# FPGA.net
KiCad netlist of a schematic drawn in Altium Designer
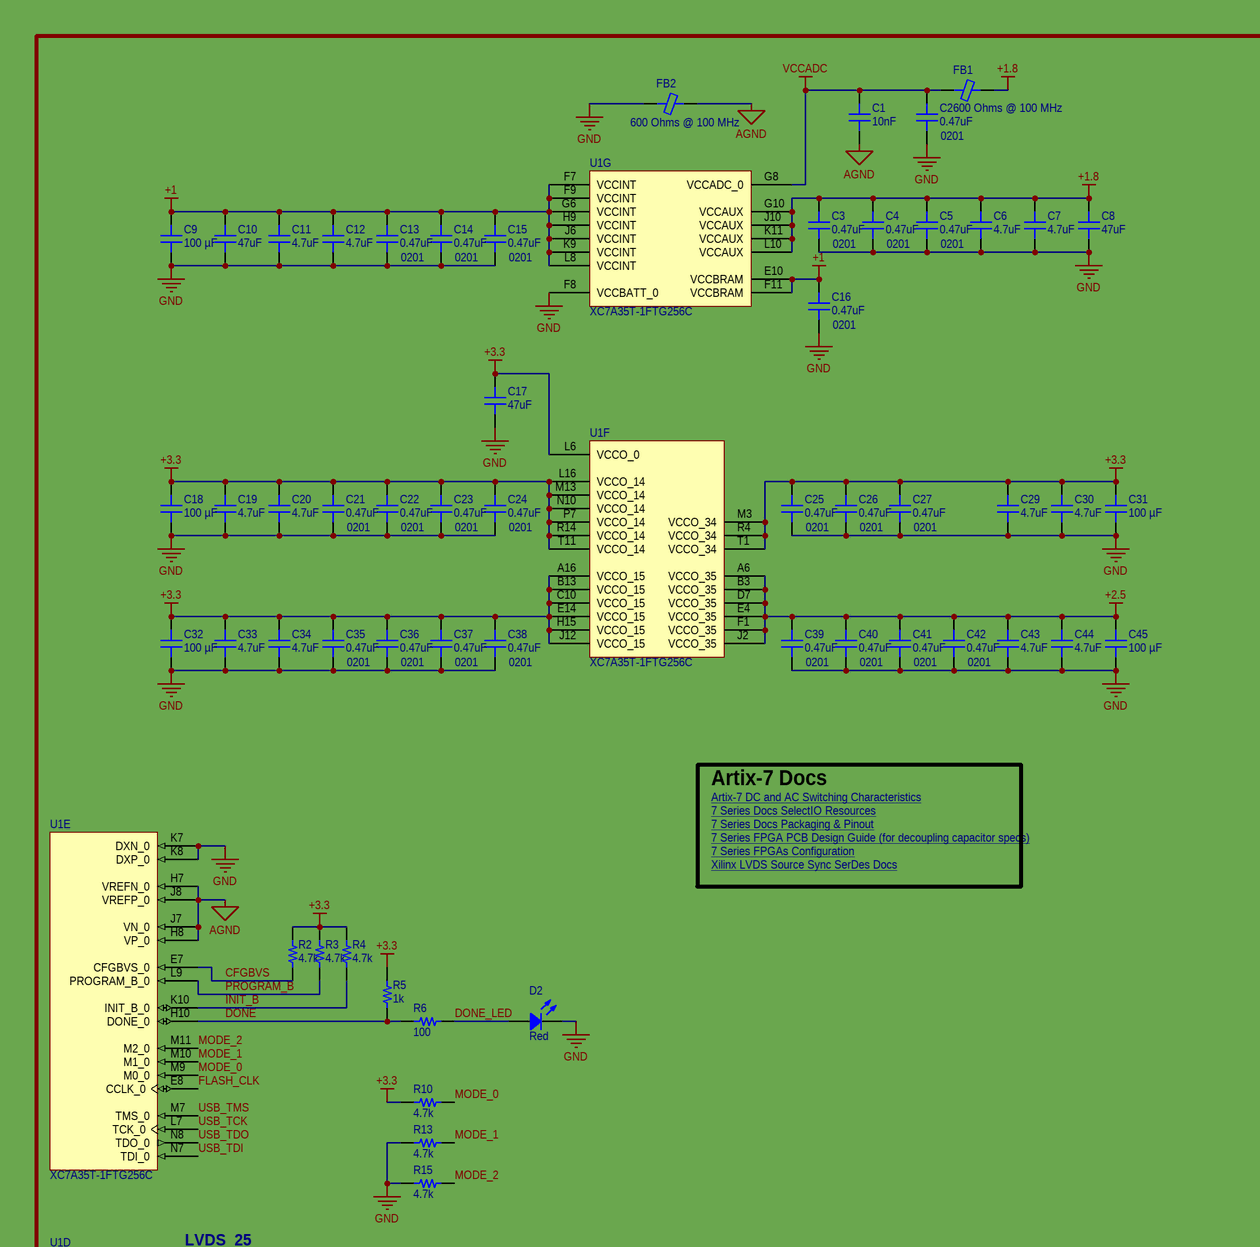
[diagram p0: FPGA.SchDoc, top left]
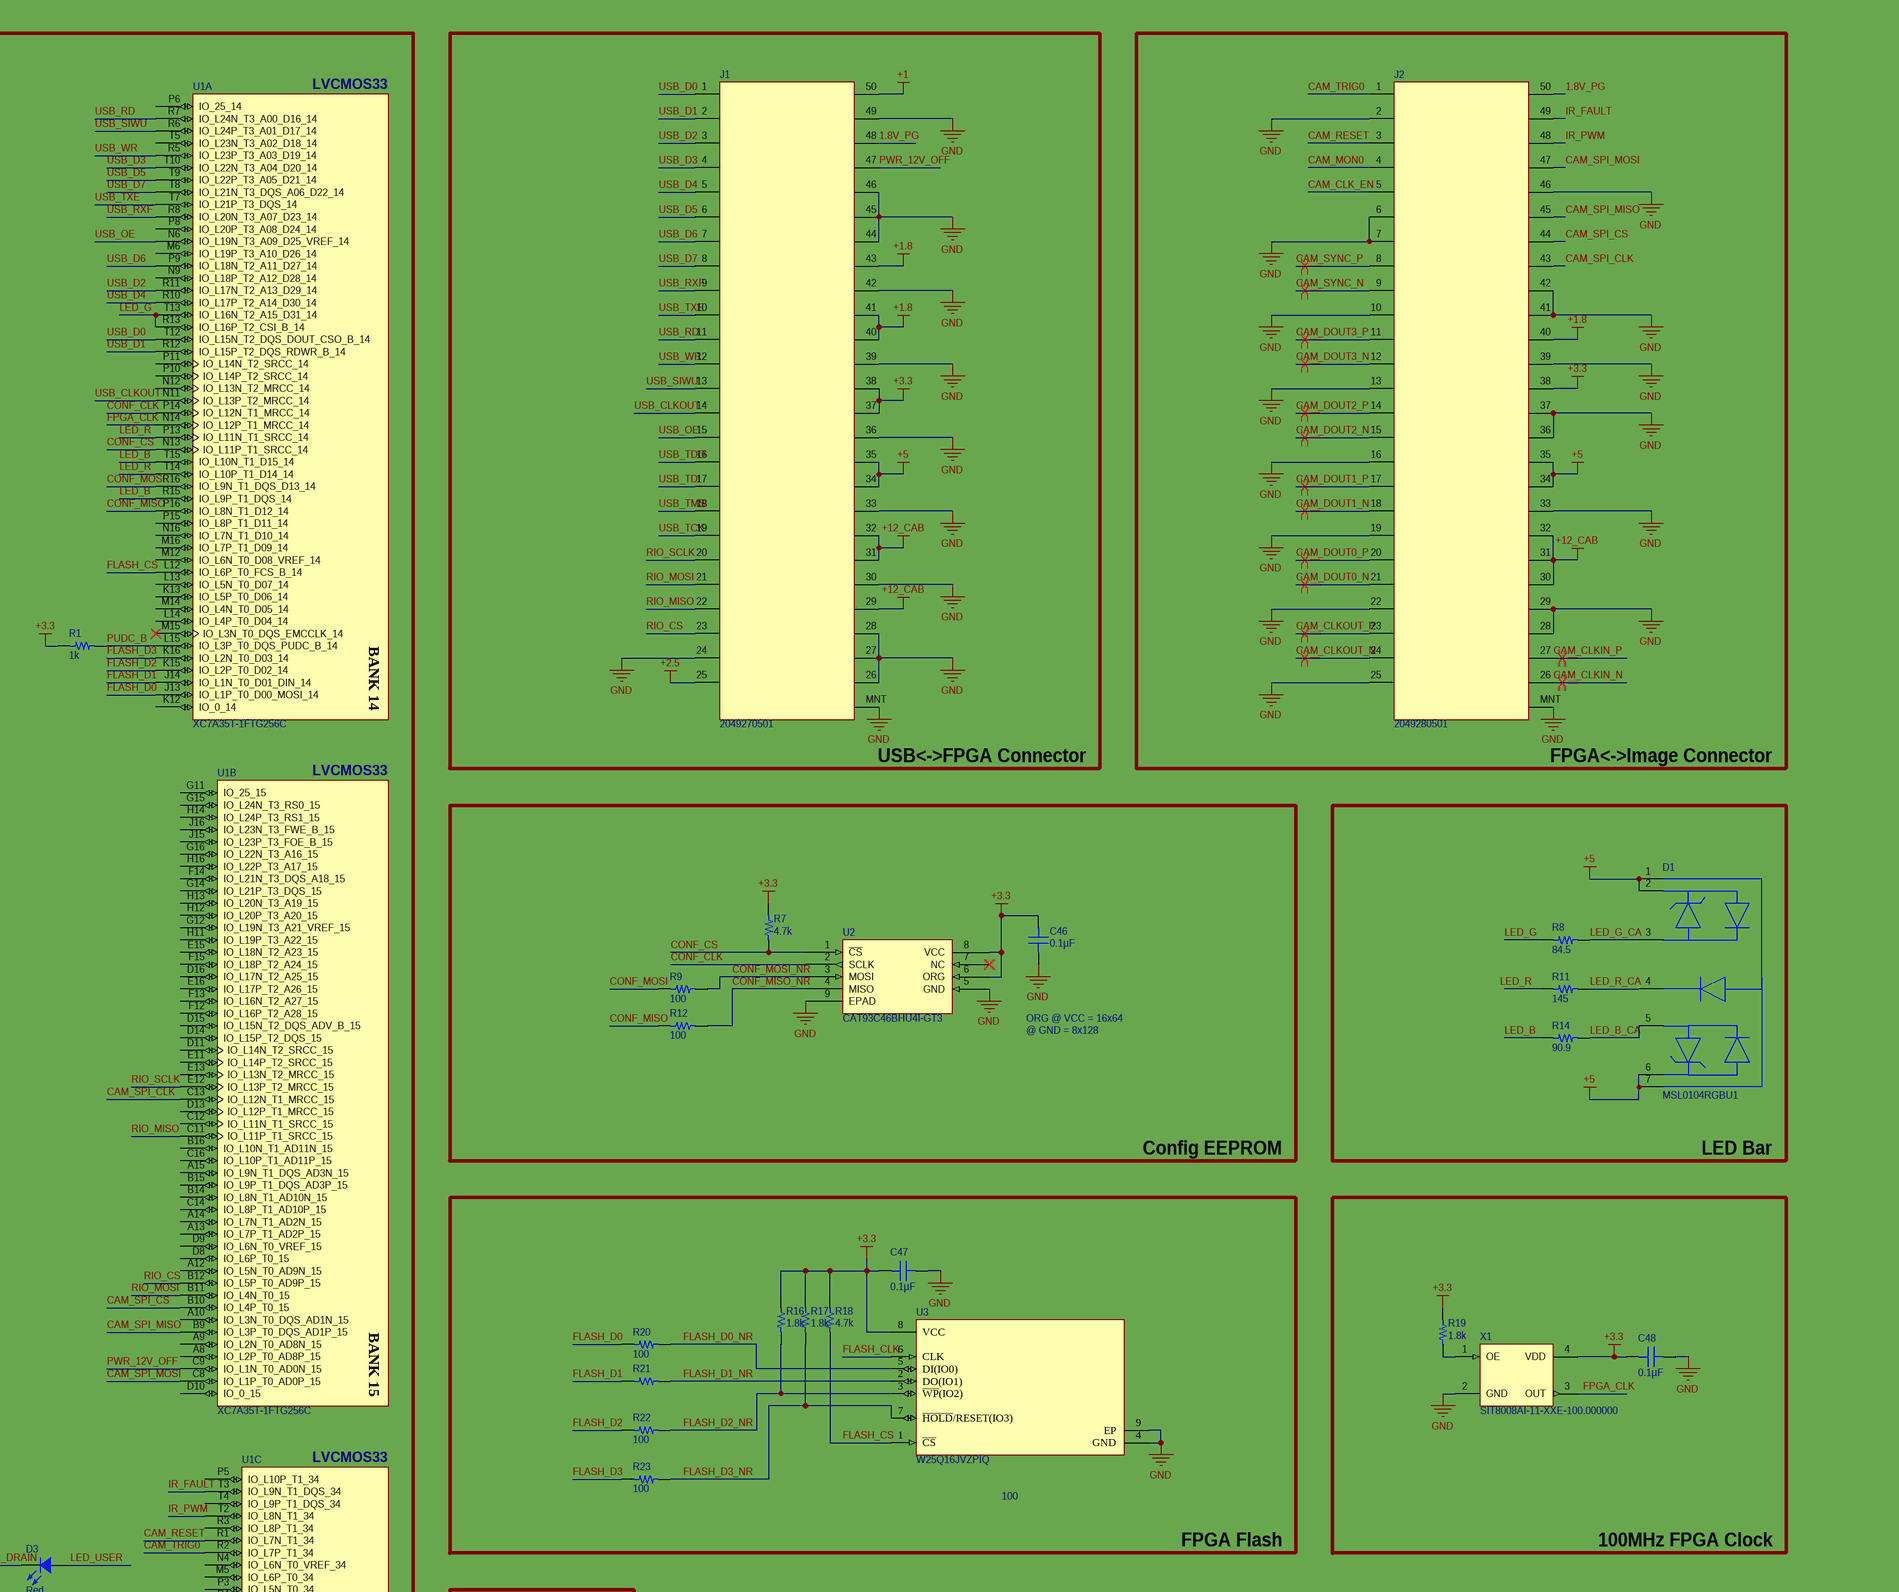
[diagram p1: FPGA.SchDoc, top middle]
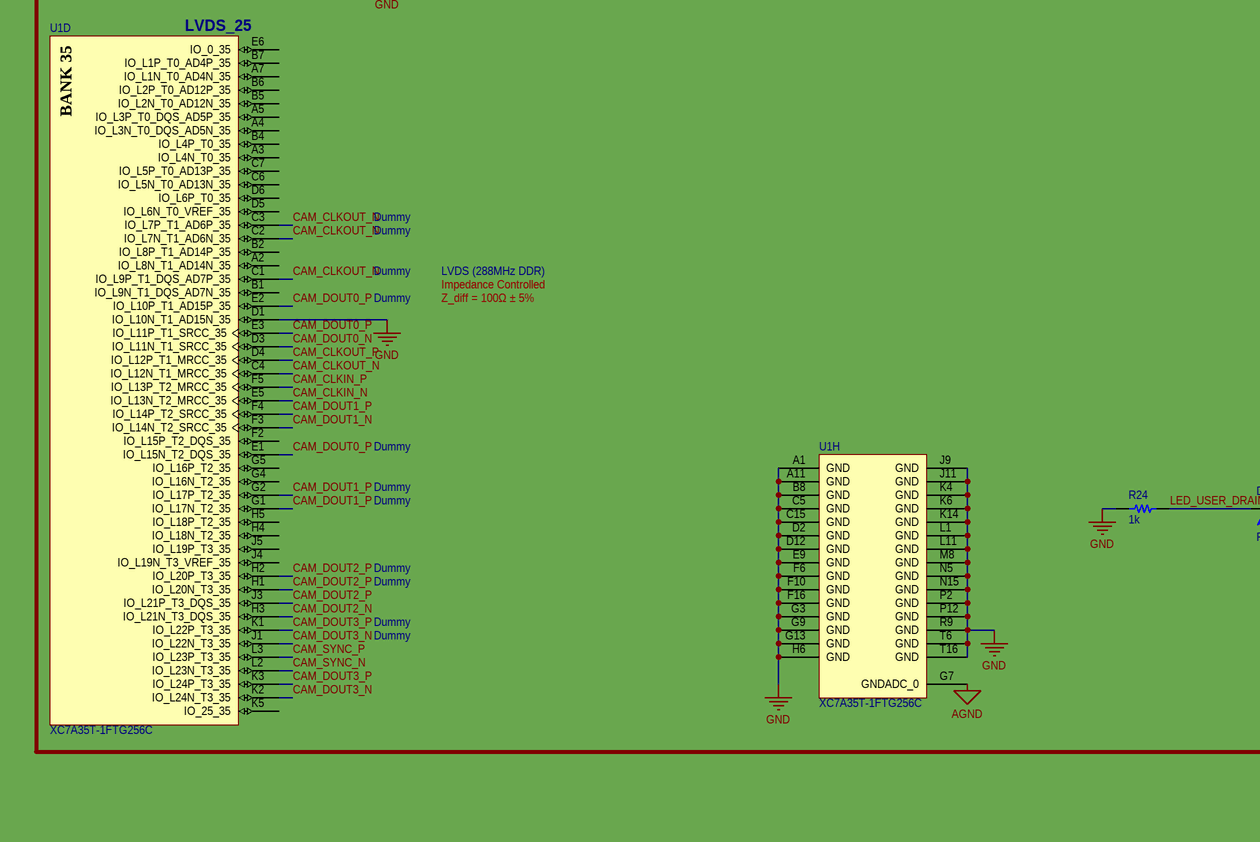
[diagram p2: FPGA.SchDoc, bottom left]
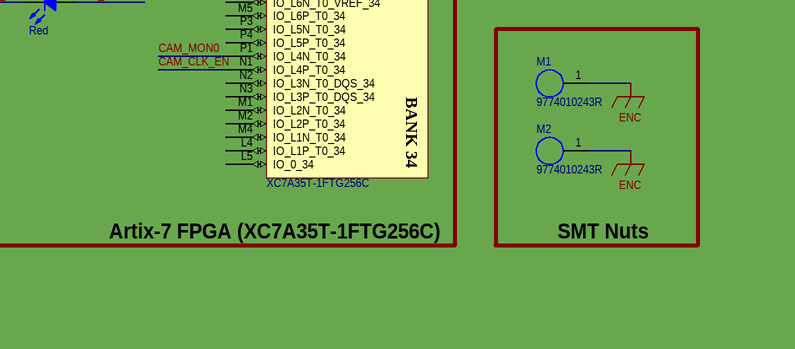
[diagram p3: FPGA.SchDoc, bottom middle]
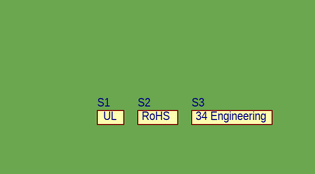
[diagram p4: FPGA.SchDoc, bottom right]

(export (version "E")
  (design (tool "Eeschema 10.0.6"))
  (components
    (comp (ref "C1")
      (value "10nF")
      (footprint "CAP 0402_1005")
      (description "CAP CER 10000PF 6.3V X7R 0402")
      (fields
        (field (name "PART NUMBER") "0402B103K6R3CT")
        (field (name "MANUFACTURER") "Walsin Technology Corporation")
      )
      (libsource (lib "altium_library") (part "Capacitor"))
    )
    (comp (ref "C2")
      (value "0.47uF")
      (footprint "CAP 0201_0603")
      (description "CAP CER 0.47UF 6.3V X5R 0201")
      (fields
        (field (name "PART NUMBER") "02016D474KAT2A")
        (field (name "MANUFACTURER") "KYOCERA AVX")
        (field (name "PACKAGE / CASE") "0201")
      )
      (libsource (lib "altium_library") (part "Capacitor"))
    )
    (comp (ref "C3")
      (value "0.47uF")
      (footprint "CAP 0201_0603")
      (description "CAP CER 0.47UF 6.3V X5R 0201")
      (fields
        (field (name "PART NUMBER") "02016D474KAT2A")
        (field (name "MANUFACTURER") "KYOCERA AVX")
        (field (name "PACKAGE / CASE") "0201")
      )
      (libsource (lib "altium_library") (part "Capacitor"))
    )
    (comp (ref "C4")
      (value "0.47uF")
      (footprint "CAP 0201_0603")
      (description "CAP CER 0.47UF 6.3V X5R 0201")
      (fields
        (field (name "PART NUMBER") "02016D474KAT2A")
        (field (name "MANUFACTURER") "KYOCERA AVX")
        (field (name "PACKAGE / CASE") "0201")
      )
      (libsource (lib "altium_library") (part "Capacitor"))
    )
    (comp (ref "C5")
      (value "0.47uF")
      (footprint "CAP 0201_0603")
      (description "CAP CER 0.47UF 6.3V X5R 0201")
      (fields
        (field (name "PART NUMBER") "02016D474KAT2A")
        (field (name "MANUFACTURER") "KYOCERA AVX")
        (field (name "PACKAGE / CASE") "0201")
      )
      (libsource (lib "altium_library") (part "Capacitor"))
    )
    (comp (ref "C6")
      (value "4.7uF")
      (footprint "CAP 0402_1005")
      (description "CAP CER 4.7UF 6.3V X5R 0402")
      (fields (field (name "PART NUMBER") "04026D475MAT2A") (field (name "MANUFACTURER") "AVX Corporation"))
      (libsource (lib "altium_library") (part "Capacitor"))
    )
    (comp (ref "C7")
      (value "4.7uF")
      (footprint "CAP 0402_1005")
      (description "CAP CER 4.7UF 6.3V X5R 0402")
      (fields (field (name "PART NUMBER") "04026D475MAT2A") (field (name "MANUFACTURER") "AVX Corporation"))
      (libsource (lib "altium_library") (part "Capacitor"))
    )
    (comp (ref "C8")
      (value "47uF")
      (footprint "CAP 0603_1608")
      (description "CAP CER 47UF 6.3V X5R 0603")
      (fields
        (field (name "PART NUMBER") "GRM188R60J476ME15D")
        (field (name "MANUFACTURER") "Murata Electronics")
      )
      (libsource (lib "altium_library") (part "Capacitor"))
    )
    (comp (ref "C9")
      (value "100 µF")
      (footprint "CAP 0805_2012")
      (description "CAP CER 100UF 6.3V X5R 0805")
      (fields
        (field (name "PART NUMBER") "GRM21BR60J107ME15L")
        (field (name "MANUFACTURER") "Murata Electronics")
      )
      (libsource (lib "altium_library") (part "Capacitor"))
    )
    (comp (ref "C10")
      (value "47uF")
      (footprint "CAP 0603_1608")
      (description "CAP CER 47UF 6.3V X5R 0603")
      (fields
        (field (name "PART NUMBER") "GRM188R60J476ME15D")
        (field (name "MANUFACTURER") "Murata Electronics")
      )
      (libsource (lib "altium_library") (part "Capacitor"))
    )
    (comp (ref "C11")
      (value "4.7uF")
      (footprint "CAP 0402_1005")
      (description "CAP CER 4.7UF 6.3V X5R 0402")
      (fields (field (name "PART NUMBER") "04026D475MAT2A") (field (name "MANUFACTURER") "AVX Corporation"))
      (libsource (lib "altium_library") (part "Capacitor"))
    )
    (comp (ref "C12")
      (value "4.7uF")
      (footprint "CAP 0402_1005")
      (description "CAP CER 4.7UF 6.3V X5R 0402")
      (fields (field (name "PART NUMBER") "04026D475MAT2A") (field (name "MANUFACTURER") "AVX Corporation"))
      (libsource (lib "altium_library") (part "Capacitor"))
    )
    (comp (ref "C13")
      (value "0.47uF")
      (footprint "CAP 0201_0603")
      (description "CAP CER 0.47UF 6.3V X5R 0201")
      (fields
        (field (name "PART NUMBER") "02016D474KAT2A")
        (field (name "MANUFACTURER") "KYOCERA AVX")
        (field (name "PACKAGE / CASE") "0201")
      )
      (libsource (lib "altium_library") (part "Capacitor"))
    )
    (comp (ref "C14")
      (value "0.47uF")
      (footprint "CAP 0201_0603")
      (description "CAP CER 0.47UF 6.3V X5R 0201")
      (fields
        (field (name "PART NUMBER") "02016D474KAT2A")
        (field (name "MANUFACTURER") "KYOCERA AVX")
        (field (name "PACKAGE / CASE") "0201")
      )
      (libsource (lib "altium_library") (part "Capacitor"))
    )
    (comp (ref "C15")
      (value "0.47uF")
      (footprint "CAP 0201_0603")
      (description "CAP CER 0.47UF 6.3V X5R 0201")
      (fields
        (field (name "PART NUMBER") "02016D474KAT2A")
        (field (name "MANUFACTURER") "KYOCERA AVX")
        (field (name "PACKAGE / CASE") "0201")
      )
      (libsource (lib "altium_library") (part "Capacitor"))
    )
    (comp (ref "C16")
      (value "0.47uF")
      (footprint "CAP 0201_0603")
      (description "CAP CER 0.47UF 6.3V X5R 0201")
      (fields
        (field (name "PART NUMBER") "02016D474KAT2A")
        (field (name "MANUFACTURER") "KYOCERA AVX")
        (field (name "PACKAGE / CASE") "0201")
      )
      (libsource (lib "altium_library") (part "Capacitor"))
    )
    (comp (ref "C17")
      (value "47uF")
      (footprint "CAP 0603_1608")
      (description "CAP CER 47UF 6.3V X5R 0603")
      (fields
        (field (name "PART NUMBER") "GRM188R60J476ME15D")
        (field (name "MANUFACTURER") "Murata Electronics")
      )
      (libsource (lib "altium_library") (part "Capacitor"))
    )
    (comp (ref "C18")
      (value "100 µF")
      (footprint "CAP 0805_2012")
      (description "CAP CER 100UF 6.3V X5R 0805")
      (fields
        (field (name "PART NUMBER") "GRM21BR60J107ME15L")
        (field (name "MANUFACTURER") "Murata Electronics")
      )
      (libsource (lib "altium_library") (part "Capacitor"))
    )
    (comp (ref "C19")
      (value "4.7uF")
      (footprint "CAP 0402_1005")
      (description "CAP CER 4.7UF 6.3V X5R 0402")
      (fields (field (name "PART NUMBER") "04026D475MAT2A") (field (name "MANUFACTURER") "AVX Corporation"))
      (libsource (lib "altium_library") (part "Capacitor"))
    )
    (comp (ref "C20")
      (value "4.7uF")
      (footprint "CAP 0402_1005")
      (description "CAP CER 4.7UF 6.3V X5R 0402")
      (fields (field (name "PART NUMBER") "04026D475MAT2A") (field (name "MANUFACTURER") "AVX Corporation"))
      (libsource (lib "altium_library") (part "Capacitor"))
    )
    (comp (ref "C21")
      (value "0.47uF")
      (footprint "CAP 0201_0603")
      (description "CAP CER 0.47UF 6.3V X5R 0201")
      (fields
        (field (name "PART NUMBER") "02016D474KAT2A")
        (field (name "MANUFACTURER") "KYOCERA AVX")
        (field (name "PACKAGE / CASE") "0201")
      )
      (libsource (lib "altium_library") (part "Capacitor"))
    )
    (comp (ref "C22")
      (value "0.47uF")
      (footprint "CAP 0201_0603")
      (description "CAP CER 0.47UF 6.3V X5R 0201")
      (fields
        (field (name "PART NUMBER") "02016D474KAT2A")
        (field (name "MANUFACTURER") "KYOCERA AVX")
        (field (name "PACKAGE / CASE") "0201")
      )
      (libsource (lib "altium_library") (part "Capacitor"))
    )
    (comp (ref "C23")
      (value "0.47uF")
      (footprint "CAP 0201_0603")
      (description "CAP CER 0.47UF 6.3V X5R 0201")
      (fields
        (field (name "PART NUMBER") "02016D474KAT2A")
        (field (name "MANUFACTURER") "KYOCERA AVX")
        (field (name "PACKAGE / CASE") "0201")
      )
      (libsource (lib "altium_library") (part "Capacitor"))
    )
    (comp (ref "C24")
      (value "0.47uF")
      (footprint "CAP 0201_0603")
      (description "CAP CER 0.47UF 6.3V X5R 0201")
      (fields
        (field (name "PART NUMBER") "02016D474KAT2A")
        (field (name "MANUFACTURER") "KYOCERA AVX")
        (field (name "PACKAGE / CASE") "0201")
      )
      (libsource (lib "altium_library") (part "Capacitor"))
    )
    (comp (ref "C25")
      (value "0.47uF")
      (footprint "CAP 0201_0603")
      (description "CAP CER 0.47UF 6.3V X5R 0201")
      (fields
        (field (name "PART NUMBER") "02016D474KAT2A")
        (field (name "MANUFACTURER") "KYOCERA AVX")
        (field (name "PACKAGE / CASE") "0201")
      )
      (libsource (lib "altium_library") (part "Capacitor"))
    )
    (comp (ref "C26")
      (value "0.47uF")
      (footprint "CAP 0201_0603")
      (description "CAP CER 0.47UF 6.3V X5R 0201")
      (fields
        (field (name "PART NUMBER") "02016D474KAT2A")
        (field (name "MANUFACTURER") "KYOCERA AVX")
        (field (name "PACKAGE / CASE") "0201")
      )
      (libsource (lib "altium_library") (part "Capacitor"))
    )
    (comp (ref "C27")
      (value "0.47uF")
      (footprint "CAP 0201_0603")
      (description "CAP CER 0.47UF 6.3V X5R 0201")
      (fields
        (field (name "PART NUMBER") "02016D474KAT2A")
        (field (name "MANUFACTURER") "KYOCERA AVX")
        (field (name "PACKAGE / CASE") "0201")
      )
      (libsource (lib "altium_library") (part "Capacitor"))
    )
    (comp (ref "C29")
      (value "4.7uF")
      (footprint "CAP 0402_1005")
      (description "CAP CER 4.7UF 6.3V X5R 0402")
      (fields (field (name "PART NUMBER") "04026D475MAT2A") (field (name "MANUFACTURER") "AVX Corporation"))
      (libsource (lib "altium_library") (part "Capacitor"))
    )
    (comp (ref "C30")
      (value "4.7uF")
      (footprint "CAP 0402_1005")
      (description "CAP CER 4.7UF 6.3V X5R 0402")
      (fields (field (name "PART NUMBER") "04026D475MAT2A") (field (name "MANUFACTURER") "AVX Corporation"))
      (libsource (lib "altium_library") (part "Capacitor"))
    )
    (comp (ref "C31")
      (value "100 µF")
      (footprint "CAP 0805_2012")
      (description "CAP CER 100UF 6.3V X5R 0805")
      (fields
        (field (name "PART NUMBER") "GRM21BR60J107ME15L")
        (field (name "MANUFACTURER") "Murata Electronics")
      )
      (libsource (lib "altium_library") (part "Capacitor"))
    )
    (comp (ref "C32")
      (value "100 µF")
      (footprint "CAP 0805_2012")
      (description "CAP CER 100UF 6.3V X5R 0805")
      (fields
        (field (name "PART NUMBER") "GRM21BR60J107ME15L")
        (field (name "MANUFACTURER") "Murata Electronics")
      )
      (libsource (lib "altium_library") (part "Capacitor"))
    )
    (comp (ref "C33")
      (value "4.7uF")
      (footprint "CAP 0402_1005")
      (description "CAP CER 4.7UF 6.3V X5R 0402")
      (fields (field (name "PART NUMBER") "04026D475MAT2A") (field (name "MANUFACTURER") "AVX Corporation"))
      (libsource (lib "altium_library") (part "Capacitor"))
    )
    (comp (ref "C34")
      (value "4.7uF")
      (footprint "CAP 0402_1005")
      (description "CAP CER 4.7UF 6.3V X5R 0402")
      (fields (field (name "PART NUMBER") "04026D475MAT2A") (field (name "MANUFACTURER") "AVX Corporation"))
      (libsource (lib "altium_library") (part "Capacitor"))
    )
    (comp (ref "C35")
      (value "0.47uF")
      (footprint "CAP 0201_0603")
      (description "CAP CER 0.47UF 6.3V X5R 0201")
      (fields
        (field (name "PART NUMBER") "02016D474KAT2A")
        (field (name "MANUFACTURER") "KYOCERA AVX")
        (field (name "PACKAGE / CASE") "0201")
      )
      (libsource (lib "altium_library") (part "Capacitor"))
    )
    (comp (ref "C36")
      (value "0.47uF")
      (footprint "CAP 0201_0603")
      (description "CAP CER 0.47UF 6.3V X5R 0201")
      (fields
        (field (name "PART NUMBER") "02016D474KAT2A")
        (field (name "MANUFACTURER") "KYOCERA AVX")
        (field (name "PACKAGE / CASE") "0201")
      )
      (libsource (lib "altium_library") (part "Capacitor"))
    )
    (comp (ref "C37")
      (value "0.47uF")
      (footprint "CAP 0201_0603")
      (description "CAP CER 0.47UF 6.3V X5R 0201")
      (fields
        (field (name "PART NUMBER") "02016D474KAT2A")
        (field (name "MANUFACTURER") "KYOCERA AVX")
        (field (name "PACKAGE / CASE") "0201")
      )
      (libsource (lib "altium_library") (part "Capacitor"))
    )
    (comp (ref "C38")
      (value "0.47uF")
      (footprint "CAP 0201_0603")
      (description "CAP CER 0.47UF 6.3V X5R 0201")
      (fields
        (field (name "PART NUMBER") "02016D474KAT2A")
        (field (name "MANUFACTURER") "KYOCERA AVX")
        (field (name "PACKAGE / CASE") "0201")
      )
      (libsource (lib "altium_library") (part "Capacitor"))
    )
    (comp (ref "C39")
      (value "0.47uF")
      (footprint "CAP 0201_0603")
      (description "CAP CER 0.47UF 6.3V X5R 0201")
      (fields
        (field (name "PART NUMBER") "02016D474KAT2A")
        (field (name "MANUFACTURER") "KYOCERA AVX")
        (field (name "PACKAGE / CASE") "0201")
      )
      (libsource (lib "altium_library") (part "Capacitor"))
    )
    (comp (ref "C40")
      (value "0.47uF")
      (footprint "CAP 0201_0603")
      (description "CAP CER 0.47UF 6.3V X5R 0201")
      (fields
        (field (name "PART NUMBER") "02016D474KAT2A")
        (field (name "MANUFACTURER") "KYOCERA AVX")
        (field (name "PACKAGE / CASE") "0201")
      )
      (libsource (lib "altium_library") (part "Capacitor"))
    )
    (comp (ref "C41")
      (value "0.47uF")
      (footprint "CAP 0201_0603")
      (description "CAP CER 0.47UF 6.3V X5R 0201")
      (fields
        (field (name "PART NUMBER") "02016D474KAT2A")
        (field (name "MANUFACTURER") "KYOCERA AVX")
        (field (name "PACKAGE / CASE") "0201")
      )
      (libsource (lib "altium_library") (part "Capacitor"))
    )
    (comp (ref "C42")
      (value "0.47uF")
      (footprint "CAP 0201_0603")
      (description "CAP CER 0.47UF 6.3V X5R 0201")
      (fields
        (field (name "PART NUMBER") "02016D474KAT2A")
        (field (name "MANUFACTURER") "KYOCERA AVX")
        (field (name "PACKAGE / CASE") "0201")
      )
      (libsource (lib "altium_library") (part "Capacitor"))
    )
    (comp (ref "C43")
      (value "4.7uF")
      (footprint "CAP 0402_1005")
      (description "CAP CER 4.7UF 6.3V X5R 0402")
      (fields (field (name "PART NUMBER") "04026D475MAT2A") (field (name "MANUFACTURER") "AVX Corporation"))
      (libsource (lib "altium_library") (part "Capacitor"))
    )
    (comp (ref "C44")
      (value "4.7uF")
      (footprint "CAP 0402_1005")
      (description "CAP CER 4.7UF 6.3V X5R 0402")
      (fields (field (name "PART NUMBER") "04026D475MAT2A") (field (name "MANUFACTURER") "AVX Corporation"))
      (libsource (lib "altium_library") (part "Capacitor"))
    )
    (comp (ref "C45")
      (value "100 µF")
      (footprint "CAP 0805_2012")
      (description "CAP CER 100UF 6.3V X5R 0805")
      (fields
        (field (name "PART NUMBER") "GRM21BR60J107ME15L")
        (field (name "MANUFACTURER") "Murata Electronics")
      )
      (libsource (lib "altium_library") (part "Capacitor"))
    )
    (comp (ref "C46")
      (value "0.1µF")
      (footprint "CAP 0402_1005")
      (description "CAP CER 0.1UF 10V X7R 0402")
      (fields (field (name "PART NUMBER") "0402ZC104KAT2A") (field (name "MANUFACTURER") "AVX Corporation"))
      (libsource (lib "altium_library") (part "Capacitor"))
    )
    (comp (ref "C47")
      (value "0.1µF")
      (footprint "CAP 0402_1005")
      (description "CAP CER 0.1UF 10V X7R 0402")
      (fields (field (name "PART NUMBER") "0402ZC104KAT2A") (field (name "MANUFACTURER") "AVX Corporation"))
      (libsource (lib "altium_library") (part "Capacitor"))
    )
    (comp (ref "C48")
      (value "0.1µF")
      (footprint "CAP 0402_1005")
      (description "CAP CER 0.1UF 10V X7R 0402")
      (fields (field (name "PART NUMBER") "0402ZC104KAT2A") (field (name "MANUFACTURER") "AVX Corporation"))
      (libsource (lib "altium_library") (part "Capacitor"))
    )
    (comp (ref "D1")
      (value "MSL0104RGBU1")
      (footprint "FP-MSL0104-MFG")
      (description "LED RGB DIFFUSED 2709 SMD R/A")
      (fields
        (field (name "OCTOPART") "https://octopart.com/msl0104rgbu1-rohm-71139759")
        (field (name "MANUFACTURER") "Rohm")
      )
      (libsource (lib "Altium Content Vault") (part "c1ae77389a615bb85b9424d60117df8"))
    )
    (comp (ref "D2")
      (value "Red")
      (footprint "LED 0603_1608 RED")
      (description "LED RED DIFFUSED 1608 SMD")
      (fields (field (name "PART NUMBER") "SML-D12U1WT86") (field (name "MANUFACTURER") "Rohm Semiconductor"))
      (libsource (lib "altium_library") (part "LED"))
    )
    (comp (ref "D3")
      (value "Red")
      (footprint "LED 0603_1608 RED")
      (description "LED RED DIFFUSED 1608 SMD")
      (fields (field (name "PART NUMBER") "SML-D12U1WT86") (field (name "MANUFACTURER") "Rohm Semiconductor"))
      (libsource (lib "altium_library") (part "LED"))
    )
    (comp (ref "FB1")
      (value "600 Ohms @ 100 MHz")
      (footprint "FER 0603_1608")
      (description "FERRITE BEAD 600 OHM 0603 1LN")
      (fields
        (field (name "PART NUMBER") "BLM18AG601SN1D")
        (field (name "MANUFACTURER") "Murata Electronics")
      )
      (libsource (lib "altium_library") (part "Ferrite Chip"))
    )
    (comp (ref "FB2")
      (value "600 Ohms @ 100 MHz")
      (footprint "FER 0603_1608")
      (description "FERRITE BEAD 600 OHM 0603 1LN")
      (fields
        (field (name "PART NUMBER") "BLM18AG601SN1D")
        (field (name "MANUFACTURER") "Murata Electronics")
      )
      (libsource (lib "altium_library") (part "Ferrite Chip"))
    )
    (comp (ref "J1")
      (value "2049270501")
      (footprint "2049270501")
      (fields (field (name "MANUFACTURER") "Molex") (field (name "MANUFACTURER PART NUMBER") "203955-0503"))
      (libsource (lib "Virtex") (part "2049270501"))
    )
    (comp (ref "J2")
      (value "2049280501")
      (footprint "2049280501")
      (fields (field (name "MANUFACTURER") "Molex") (field (name "MANUFACTURER PART NUMBER") "203955-0503"))
      (libsource (lib "Virtex") (part "2049280501"))
    )
    (comp (ref "M1")
      (value "9774010243R")
      (footprint "9774010243R")
      (description "Spacer Material: Steel, Tin-Plated Mounting: SMT Series: WA-SMST Thread D: M2")
      (fields
        (field (name "MANUFACTURER") "Wurth Electronics")
        (field (name "MANUFACTURER PART NUMBER") "9774070960R")
      )
      (libsource (lib "Virtex") (part "9774010243R"))
    )
    (comp (ref "M2")
      (value "9774010243R")
      (footprint "9774010243R")
      (description "Spacer Material: Steel, Tin-Plated Mounting: SMT Series: WA-SMST Thread D: M2")
      (fields
        (field (name "MANUFACTURER") "Wurth Electronics")
        (field (name "MANUFACTURER PART NUMBER") "9774070960R")
      )
      (libsource (lib "Virtex") (part "9774010243R"))
    )
    (comp (ref "R1")
      (value "1k")
      (footprint "RES 0402_1005")
      (description "RES 1 KOHMS 0.1% 1/16W 0402")
      (fields
        (field (name "PART NUMBER") "RQ73C1E1K0BTD")
        (field (name "MANUFACTURER") "TE Connectivity Passive Product")
      )
      (libsource (lib "altium_library") (part "Resistor"))
    )
    (comp (ref "R2")
      (value "4.7k")
      (footprint "RES 0402_1005")
      (description "RES 4.7K OHM 1% 1/16W 0402")
      (fields
        (field (name "PART NUMBER") "RMCF0402FT4K70")
        (field (name "MANUFACTURER") "Stackpole Electronics Inc")
      )
      (libsource (lib "altium_library") (part "Resistor"))
    )
    (comp (ref "R3")
      (value "4.7k")
      (footprint "RES 0402_1005")
      (description "RES 4.7K OHM 1% 1/16W 0402")
      (fields
        (field (name "PART NUMBER") "RMCF0402FT4K70")
        (field (name "MANUFACTURER") "Stackpole Electronics Inc")
      )
      (libsource (lib "altium_library") (part "Resistor"))
    )
    (comp (ref "R4")
      (value "4.7k")
      (footprint "RES 0402_1005")
      (description "RES 4.7K OHM 1% 1/16W 0402")
      (fields
        (field (name "PART NUMBER") "RMCF0402FT4K70")
        (field (name "MANUFACTURER") "Stackpole Electronics Inc")
      )
      (libsource (lib "altium_library") (part "Resistor"))
    )
    (comp (ref "R5")
      (value "1k")
      (footprint "RES 0402_1005")
      (description "RES 1K OHM 1% 1/10W 0402")
      (fields
        (field (name "PART NUMBER") "RK73H1ETTP1001F")
        (field (name "MANUFACTURER") "KOA Speer Electronics, Inc.")
      )
      (libsource (lib "altium_library") (part "Resistor"))
    )
    (comp (ref "R6")
      (value "100")
      (footprint "RES 0402_1005")
      (description "RES SMD 100 OHM 1% 1/16W 0402")
      (fields (field (name "PART NUMBER") "RCA0402100RFKED") (field (name "MANUFACTURER") "Vishay Dale"))
      (libsource (lib "altium_library") (part "Resistor"))
    )
    (comp (ref "R7")
      (value "4.7k")
      (footprint "RES 0402_1005")
      (description "RES 4.7K OHM 1% 1/16W 0402")
      (fields
        (field (name "PART NUMBER") "RMCF0402FT4K70")
        (field (name "MANUFACTURER") "Stackpole Electronics Inc")
      )
      (libsource (lib "altium_library") (part "Resistor"))
    )
    (comp (ref "R8")
      (value "84.5")
      (footprint "RES 0402_1005")
      (description "RES 84.5 OHM 1% 1/16W 0402")
      (fields (field (name "PART NUMBER") "RC0402FR-0784R5L") (field (name "MANUFACTURER") "Yageo"))
      (libsource (lib "altium_library") (part "Resistor"))
    )
    (comp (ref "R9")
      (value "100")
      (footprint "RES 0402_1005")
      (description "RES SMD 100 OHM 1% 1/16W 0402")
      (fields (field (name "PART NUMBER") "RCA0402100RFKED") (field (name "MANUFACTURER") "Vishay Dale"))
      (libsource (lib "altium_library") (part "Resistor"))
    )
    (comp (ref "R10")
      (value "4.7k")
      (footprint "RES 0402_1005")
      (description "RES 4.7K OHM 1% 1/16W 0402")
      (fields
        (field (name "PART NUMBER") "RMCF0402FT4K70")
        (field (name "MANUFACTURER") "Stackpole Electronics Inc")
      )
      (libsource (lib "altium_library") (part "Resistor"))
    )
    (comp (ref "R11")
      (value "145")
      (footprint "RES 0402_1005")
      (description "RES 145 OHM 0.1% 1/16W 0402")
      (fields
        (field (name "PART NUMBER") "RN73R1ETTP1450B25")
        (field (name "MANUFACTURER") "KOA Speer Electronics, Inc.")
      )
      (libsource (lib "altium_library") (part "Resistor"))
    )
    (comp (ref "R12")
      (value "100")
      (footprint "RES 0402_1005")
      (description "RES SMD 100 OHM 1% 1/16W 0402")
      (fields (field (name "PART NUMBER") "RCA0402100RFKED") (field (name "MANUFACTURER") "Vishay Dale"))
      (libsource (lib "altium_library") (part "Resistor"))
    )
    (comp (ref "R13")
      (value "4.7k")
      (footprint "RES 0402_1005")
      (description "RES 4.7K OHM 1% 1/16W 0402")
      (fields
        (field (name "PART NUMBER") "RMCF0402FT4K70")
        (field (name "MANUFACTURER") "Stackpole Electronics Inc")
      )
      (libsource (lib "altium_library") (part "Resistor"))
    )
    (comp (ref "R14")
      (value "90.9")
      (footprint "RES 0402_1005")
      (description "RES 90.9 OHM 1% 1/16W 0402")
      (fields
        (field (name "PART NUMBER") "RMCF0402FT90R9")
        (field (name "MANUFACTURER") "Stackpole Electronics Inc")
      )
      (libsource (lib "altium_library") (part "Resistor"))
    )
    (comp (ref "R15")
      (value "4.7k")
      (footprint "RES 0402_1005")
      (description "RES 4.7K OHM 1% 1/16W 0402")
      (fields
        (field (name "PART NUMBER") "RMCF0402FT4K70")
        (field (name "MANUFACTURER") "Stackpole Electronics Inc")
      )
      (libsource (lib "altium_library") (part "Resistor"))
    )
    (comp (ref "R16")
      (value "1.8k")
      (footprint "RES 0402_1005")
      (description "RES 1.8K OHM 1% 1/16W 0402")
      (fields (field (name "PART NUMBER") "RC0402FR-071K8L") (field (name "MANUFACTURER") "Yageo"))
      (libsource (lib "altium_library") (part "Resistor"))
    )
    (comp (ref "R17")
      (value "1.8k")
      (footprint "RES 0402_1005")
      (description "RES 1.8K OHM 1% 1/16W 0402")
      (fields (field (name "PART NUMBER") "RC0402FR-071K8L") (field (name "MANUFACTURER") "Yageo"))
      (libsource (lib "altium_library") (part "Resistor"))
    )
    (comp (ref "R18")
      (value "4.7k")
      (footprint "RES 0402_1005")
      (description "RES 4.7K OHM 1% 1/16W 0402")
      (fields
        (field (name "PART NUMBER") "RMCF0402FT4K70")
        (field (name "MANUFACTURER") "Stackpole Electronics Inc")
      )
      (libsource (lib "altium_library") (part "Resistor"))
    )
    (comp (ref "R19")
      (value "1.8k")
      (footprint "RES 0402_1005")
      (description "RES 1.8K OHM 1% 1/16W 0402")
      (fields (field (name "PART NUMBER") "RC0402FR-071K8L") (field (name "MANUFACTURER") "Yageo"))
      (libsource (lib "altium_library") (part "Resistor"))
    )
    (comp (ref "R20")
      (value "100")
      (footprint "RES 0402_1005")
      (description "RES SMD 100 OHM 1% 1/16W 0402")
      (fields (field (name "PART NUMBER") "RCA0402100RFKED") (field (name "MANUFACTURER") "Vishay Dale"))
      (libsource (lib "altium_library") (part "Resistor"))
    )
    (comp (ref "R21")
      (value "100")
      (footprint "RES 0402_1005")
      (description "RES SMD 100 OHM 1% 1/16W 0402")
      (fields (field (name "PART NUMBER") "RCA0402100RFKED") (field (name "MANUFACTURER") "Vishay Dale"))
      (libsource (lib "altium_library") (part "Resistor"))
    )
    (comp (ref "R22")
      (value "100")
      (footprint "RES 0402_1005")
      (description "RES SMD 100 OHM 1% 1/16W 0402")
      (fields (field (name "PART NUMBER") "RCA0402100RFKED") (field (name "MANUFACTURER") "Vishay Dale"))
      (libsource (lib "altium_library") (part "Resistor"))
    )
    (comp (ref "R23")
      (value "100")
      (footprint "RES 0402_1005")
      (description "RES SMD 100 OHM 1% 1/16W 0402")
      (fields (field (name "PART NUMBER") "RCA0402100RFKED") (field (name "MANUFACTURER") "Vishay Dale"))
      (libsource (lib "altium_library") (part "Resistor"))
    )
    (comp (ref "R24")
      (value "1k")
      (footprint "RES 0603_1608")
      (description "RES SMD 1K OHM 1% 1/10W 0603")
      (fields (field (name "PART NUMBER") "CRCW06031K00FKEB") (field (name "MANUFACTURER") "Vishay Dale"))
      (libsource (lib "altium_library") (part "Resistor"))
    )
    (comp (ref "S1") (value "~") (footprint "UL") (libsource (lib "Virtex") (part "UL")))
    (comp (ref "S2") (value "~") (footprint "RoHS") (libsource (lib "Virtex") (part "RoHS")))
    (comp (ref "S3")
      (value "~")
      (footprint "34EngineeringLogo")
      (description "34 Engineering Silkscreen Logo")
      (libsource (lib "Virtex") (part "34EngineeringLogo"))
    )
    (comp (ref "U1")
      (value "XC7A35T-1FTG256C")
      (footprint "FTG256")
      (description "Artix-7 FPGA, 170 User I/Os, 0 GTP, 256-Ball BGA, Speed Grade 1, Commercial Grade, Pb-Free")
      (fields (field (name "MANUFACTURER") "Xilinx"))
      (libsource (lib "") (part "XLNX-XC7A35T-FTG256_1"))
    )
    (comp (ref "U2")
      (value "CAT93C46BHU4I-GT3")
      (footprint "CAT93C46BHU4I-GT3")
      (description "EEPROM Memory IC 1Kb (128 x 8, 64 x 16) SPI 4 MHz 8-UDFN-EP (2x3)")
      (libsource (lib "Virtex") (part "CAT93C46BHU4I-GT3"))
    )
    (comp (ref "U3")
      (value "W25Q16JVZPIQ")
      (footprint "FP-ZP-IPC_B")
      (description "IC FLASH 16MBIT SPI/QUAD 8WSON")
      (libsource (lib "Altium Content Vault") (part "4cb77c13ae9adfb05a25f85e82aeb43"))
    )
    (comp (ref "X1")
      (value "SIT8008AI-11-XXE-100.000000")
      (footprint "SIT8008AI-11-XXE-100.000000")
      (fields
        (field (name "MANUFACTURER") "SiTime")
        (field (name "MANUFACTURER PART NUMBER") "SIT8008AI-11-XXE-100.000000E")
      )
      (libsource (lib "Virtex") (part "SIT8008AI-11-XXE-100.000000"))
    )
  )
  (nets
    (net (code "1") (name "+1") (class "Default")
      (node (ref "C10") (pin "2") (pinfunction "2_2") (pintype "passive"))
      (node (ref "C11") (pin "1") (pinfunction "1_1") (pintype "passive"))
      (node (ref "C12") (pin "1") (pinfunction "1_1") (pintype "passive"))
      (node (ref "C13") (pin "1") (pinfunction "1_1") (pintype "passive"))
      (node (ref "C14") (pin "1") (pinfunction "1_1") (pintype "passive"))
      (node (ref "C15") (pin "1") (pinfunction "1_1") (pintype "passive"))
      (node (ref "C16") (pin "2") (pinfunction "2_2") (pintype "passive"))
      (node (ref "C9") (pin "2") (pinfunction "2_2") (pintype "passive"))
      (node (ref "J1") (pin "50") (pintype "passive"))
      (node (ref "U1") (pin "E10") (pinfunction "VCCBRAM_E10") (pintype "power_in"))
      (node (ref "U1") (pin "F11") (pinfunction "VCCBRAM_F11") (pintype "power_in"))
      (node (ref "U1") (pin "F7") (pinfunction "VCCINT_F7") (pintype "power_in"))
      (node (ref "U1") (pin "F9") (pinfunction "VCCINT_F9") (pintype "power_in"))
      (node (ref "U1") (pin "G6") (pinfunction "VCCINT_G6") (pintype "power_in"))
      (node (ref "U1") (pin "H9") (pinfunction "VCCINT_H9") (pintype "power_in"))
      (node (ref "U1") (pin "J6") (pinfunction "VCCINT_J6") (pintype "power_in"))
      (node (ref "U1") (pin "K9") (pinfunction "VCCINT_K9") (pintype "power_in"))
      (node (ref "U1") (pin "L8") (pinfunction "VCCINT_L8") (pintype "power_in"))
    )
    (net (code "2") (name "+1.8") (class "Default")
      (node (ref "C3") (pin "2") (pinfunction "2_2") (pintype "passive"))
      (node (ref "C4") (pin "2") (pinfunction "2_2") (pintype "passive"))
      (node (ref "C5") (pin "2") (pinfunction "2_2") (pintype "passive"))
      (node (ref "C6") (pin "2") (pinfunction "2_2") (pintype "passive"))
      (node (ref "C7") (pin "2") (pinfunction "2_2") (pintype "passive"))
      (node (ref "C8") (pin "2") (pinfunction "2_2") (pintype "passive"))
      (node (ref "FB1") (pin "2") (pinfunction "2_2") (pintype "passive"))
      (node (ref "J1") (pin "40") (pintype "passive"))
      (node (ref "J1") (pin "41") (pintype "passive"))
      (node (ref "J1") (pin "43") (pintype "passive"))
      (node (ref "J2") (pin "40") (pintype "passive"))
      (node (ref "U1") (pin "G10") (pinfunction "VCCAUX_G10") (pintype "power_in"))
      (node (ref "U1") (pin "J10") (pinfunction "VCCAUX_J10") (pintype "power_in"))
      (node (ref "U1") (pin "K11") (pinfunction "VCCAUX_K11") (pintype "power_in"))
      (node (ref "U1") (pin "L10") (pinfunction "VCCAUX_L10") (pintype "power_in"))
    )
    (net (code "3") (name "+2.5") (class "Default")
      (node (ref "C39") (pin "2") (pinfunction "2_2") (pintype "passive"))
      (node (ref "C40") (pin "2") (pinfunction "2_2") (pintype "passive"))
      (node (ref "C41") (pin "2") (pinfunction "2_2") (pintype "passive"))
      (node (ref "C42") (pin "2") (pinfunction "2_2") (pintype "passive"))
      (node (ref "C43") (pin "2") (pinfunction "2_2") (pintype "passive"))
      (node (ref "C44") (pin "2") (pinfunction "2_2") (pintype "passive"))
      (node (ref "C45") (pin "2") (pinfunction "2_2") (pintype "passive"))
      (node (ref "J1") (pin "25") (pintype "passive"))
      (node (ref "U1") (pin "A6") (pinfunction "VCCO_35_A6") (pintype "power_in"))
      (node (ref "U1") (pin "B3") (pinfunction "VCCO_35_B3") (pintype "power_in"))
      (node (ref "U1") (pin "D7") (pinfunction "VCCO_35_D7") (pintype "power_in"))
      (node (ref "U1") (pin "E4") (pinfunction "VCCO_35_E4") (pintype "power_in"))
      (node (ref "U1") (pin "F1") (pinfunction "VCCO_35_F1") (pintype "power_in"))
      (node (ref "U1") (pin "J2") (pinfunction "VCCO_35_J2") (pintype "power_in"))
    )
    (net (code "4") (name "+3.3") (class "Default")
      (node (ref "C17") (pin "2") (pinfunction "2_2") (pintype "passive"))
      (node (ref "C18") (pin "2") (pinfunction "2_2") (pintype "passive"))
      (node (ref "C19") (pin "1") (pinfunction "1_1") (pintype "passive"))
      (node (ref "C20") (pin "1") (pinfunction "1_1") (pintype "passive"))
      (node (ref "C21") (pin "1") (pinfunction "1_1") (pintype "passive"))
      (node (ref "C22") (pin "1") (pinfunction "1_1") (pintype "passive"))
      (node (ref "C23") (pin "1") (pinfunction "1_1") (pintype "passive"))
      (node (ref "C24") (pin "1") (pinfunction "1_1") (pintype "passive"))
      (node (ref "C25") (pin "2") (pinfunction "2_2") (pintype "passive"))
      (node (ref "C26") (pin "2") (pinfunction "2_2") (pintype "passive"))
      (node (ref "C27") (pin "2") (pinfunction "2_2") (pintype "passive"))
      (node (ref "C29") (pin "2") (pinfunction "2_2") (pintype "passive"))
      (node (ref "C30") (pin "2") (pinfunction "2_2") (pintype "passive"))
      (node (ref "C31") (pin "2") (pinfunction "2_2") (pintype "passive"))
      (node (ref "C32") (pin "2") (pinfunction "2_2") (pintype "passive"))
      (node (ref "C33") (pin "1") (pinfunction "1_1") (pintype "passive"))
      (node (ref "C34") (pin "1") (pinfunction "1_1") (pintype "passive"))
      (node (ref "C35") (pin "1") (pinfunction "1_1") (pintype "passive"))
      (node (ref "C36") (pin "1") (pinfunction "1_1") (pintype "passive"))
      (node (ref "C37") (pin "1") (pinfunction "1_1") (pintype "passive"))
      (node (ref "C38") (pin "1") (pinfunction "1_1") (pintype "passive"))
      (node (ref "C46") (pin "2") (pinfunction "2_2") (pintype "passive"))
      (node (ref "C47") (pin "2") (pinfunction "2_2") (pintype "passive"))
      (node (ref "C48") (pin "2") (pinfunction "2_2") (pintype "passive"))
      (node (ref "J1") (pin "37") (pintype "passive"))
      (node (ref "J1") (pin "38") (pintype "passive"))
      (node (ref "J2") (pin "38") (pintype "passive"))
      (node (ref "R1") (pin "1") (pinfunction "1_1") (pintype "passive"))
      (node (ref "R10") (pin "2") (pinfunction "2_2") (pintype "passive"))
      (node (ref "R16") (pin "2") (pinfunction "2_2") (pintype "passive"))
      (node (ref "R17") (pin "2") (pinfunction "2_2") (pintype "passive"))
      (node (ref "R18") (pin "2") (pinfunction "2_2") (pintype "passive"))
      (node (ref "R19") (pin "2") (pinfunction "2_2") (pintype "passive"))
      (node (ref "R2") (pin "2") (pinfunction "2_2") (pintype "passive"))
      (node (ref "R3") (pin "2") (pinfunction "2_2") (pintype "passive"))
      (node (ref "R4") (pin "2") (pinfunction "2_2") (pintype "passive"))
      (node (ref "R5") (pin "2") (pinfunction "2_2") (pintype "passive"))
      (node (ref "R7") (pin "2") (pinfunction "2_2") (pintype "passive"))
      (node (ref "U1") (pin "A16") (pinfunction "VCCO_15_A16") (pintype "power_in"))
      (node (ref "U1") (pin "B13") (pinfunction "VCCO_15_B13") (pintype "power_in"))
      (node (ref "U1") (pin "C10") (pinfunction "VCCO_15_C10") (pintype "power_in"))
      (node (ref "U1") (pin "E14") (pinfunction "VCCO_15_E14") (pintype "power_in"))
      (node (ref "U1") (pin "H15") (pinfunction "VCCO_15_H15") (pintype "power_in"))
      (node (ref "U1") (pin "J12") (pinfunction "VCCO_15_J12") (pintype "power_in"))
      (node (ref "U1") (pin "L16") (pinfunction "VCCO_14_L16") (pintype "power_in"))
      (node (ref "U1") (pin "L6") (pinfunction "VCCO_0_L6") (pintype "power_in"))
      (node (ref "U1") (pin "M13") (pinfunction "VCCO_14_M13") (pintype "power_in"))
      (node (ref "U1") (pin "M3") (pinfunction "VCCO_34_M3") (pintype "power_in"))
      (node (ref "U1") (pin "N10") (pinfunction "VCCO_14_N10") (pintype "power_in"))
      (node (ref "U1") (pin "P7") (pinfunction "VCCO_14_P7") (pintype "power_in"))
      (node (ref "U1") (pin "R14") (pinfunction "VCCO_14_R14") (pintype "power_in"))
      (node (ref "U1") (pin "R4") (pinfunction "VCCO_34_R4") (pintype "power_in"))
      (node (ref "U1") (pin "T1") (pinfunction "VCCO_34_T1") (pintype "power_in"))
      (node (ref "U1") (pin "T11") (pinfunction "VCCO_14_T11") (pintype "power_in"))
      (node (ref "U2") (pin "6") (pinfunction "ORG_6") (pintype "input"))
      (node (ref "U2") (pin "8") (pinfunction "VCC_8") (pintype "power_in"))
      (node (ref "U3") (pin "8") (pinfunction "VCC_8") (pintype "power_in"))
      (node (ref "X1") (pin "4") (pinfunction "VDD_4") (pintype "power_in"))
    )
    (net (code "5") (name "+5") (class "Default")
      (node (ref "D1") (pin "1") (pinfunction "R_A_1") (pintype "passive"))
      (node (ref "D1") (pin "2") (pinfunction "G_A_2") (pintype "passive"))
      (node (ref "D1") (pin "6") (pinfunction "B_A_6") (pintype "passive"))
      (node (ref "D1") (pin "7") (pinfunction "R_A_7") (pintype "passive"))
      (node (ref "J1") (pin "34") (pintype "passive"))
      (node (ref "J1") (pin "35") (pintype "passive"))
      (node (ref "J2") (pin "34") (pintype "passive"))
      (node (ref "J2") (pin "35") (pintype "passive"))
    )
    (net (code "6") (name "+12_CAB") (class "Default")
      (node (ref "J1") (pin "29") (pintype "passive"))
      (node (ref "J1") (pin "31") (pintype "passive"))
      (node (ref "J1") (pin "32") (pintype "passive"))
      (node (ref "J2") (pin "30") (pintype "passive"))
      (node (ref "J2") (pin "31") (pintype "passive"))
      (node (ref "J2") (pin "32") (pintype "passive"))
    )
    (net (code "7") (name "/1.8V_PG") (class "Default")
      (node (ref "J1") (pin "48") (pintype "passive"))
      (node (ref "J2") (pin "50") (pintype "passive"))
    )
    (net (code "8") (name "/CAM_CLKIN_N") (class "Default")
      (node (ref "J2") (pin "26") (pintype "passive"))
      (node (ref "U1") (pin "E5") (pinfunction "IO_L13N_T2_MRCC_35_E5") (pintype "bidirectional"))
    )
    (net (code "9") (name "/CAM_CLKIN_P") (class "Default")
      (node (ref "J2") (pin "27") (pintype "passive"))
      (node (ref "U1") (pin "F5") (pinfunction "IO_L13P_T2_MRCC_35_F5") (pintype "bidirectional"))
    )
    (net (code "10") (name "/CAM_CLKOUT_N") (class "Default")
      (node (ref "J2") (pin "24") (pintype "passive"))
      (node (ref "U1") (pin "C1") (pinfunction "IO_L9P_T1_DQS_AD7P_35_C1") (pintype "bidirectional"))
      (node (ref "U1") (pin "C2") (pinfunction "IO_L7N_T1_AD6N_35_C2") (pintype "bidirectional"))
      (node (ref "U1") (pin "C3") (pinfunction "IO_L7P_T1_AD6P_35_C3") (pintype "bidirectional"))
      (node (ref "U1") (pin "C4") (pinfunction "IO_L12N_T1_MRCC_35_C4") (pintype "bidirectional"))
    )
    (net (code "11") (name "/CAM_CLKOUT_P") (class "Default")
      (node (ref "J2") (pin "23") (pintype "passive"))
      (node (ref "U1") (pin "D4") (pinfunction "IO_L12P_T1_MRCC_35_D4") (pintype "bidirectional"))
    )
    (net (code "12") (name "/CAM_CLK_EN") (class "Default")
      (node (ref "J2") (pin "5") (pintype "passive"))
      (node (ref "U1") (pin "N1") (pinfunction "IO_L4P_T0_34_N1") (pintype "bidirectional"))
    )
    (net (code "13") (name "/CAM_DOUT0_N") (class "Default")
      (node (ref "J2") (pin "21") (pintype "passive"))
      (node (ref "U1") (pin "D3") (pinfunction "IO_L11N_T1_SRCC_35_D3") (pintype "bidirectional"))
    )
    (net (code "14") (name "/CAM_DOUT0_P") (class "Default")
      (node (ref "J2") (pin "20") (pintype "passive"))
      (node (ref "U1") (pin "E1") (pinfunction "IO_L15N_T2_DQS_35_E1") (pintype "bidirectional"))
      (node (ref "U1") (pin "E2") (pinfunction "IO_L10P_T1_AD15P_35_E2") (pintype "bidirectional"))
      (node (ref "U1") (pin "E3") (pinfunction "IO_L11P_T1_SRCC_35_E3") (pintype "bidirectional"))
    )
    (net (code "15") (name "/CAM_DOUT1_N") (class "Default")
      (node (ref "J2") (pin "18") (pintype "passive"))
      (node (ref "U1") (pin "F3") (pinfunction "IO_L14N_T2_SRCC_35_F3") (pintype "bidirectional"))
    )
    (net (code "16") (name "/CAM_DOUT1_P") (class "Default")
      (node (ref "J2") (pin "17") (pintype "passive"))
      (node (ref "U1") (pin "F4") (pinfunction "IO_L14P_T2_SRCC_35_F4") (pintype "bidirectional"))
      (node (ref "U1") (pin "G1") (pinfunction "IO_L17N_T2_35_G1") (pintype "bidirectional"))
      (node (ref "U1") (pin "G2") (pinfunction "IO_L17P_T2_35_G2") (pintype "bidirectional"))
    )
    (net (code "17") (name "/CAM_DOUT2_N") (class "Default")
      (node (ref "J2") (pin "15") (pintype "passive"))
      (node (ref "U1") (pin "H3") (pinfunction "IO_L21N_T3_DQS_35_H3") (pintype "bidirectional"))
    )
    (net (code "18") (name "/CAM_DOUT2_P") (class "Default")
      (node (ref "J2") (pin "14") (pintype "passive"))
      (node (ref "U1") (pin "H1") (pinfunction "IO_L20N_T3_35_H1") (pintype "bidirectional"))
      (node (ref "U1") (pin "H2") (pinfunction "IO_L20P_T3_35_H2") (pintype "bidirectional"))
      (node (ref "U1") (pin "J3") (pinfunction "IO_L21P_T3_DQS_35_J3") (pintype "bidirectional"))
    )
    (net (code "19") (name "/CAM_DOUT3_N") (class "Default")
      (node (ref "J2") (pin "12") (pintype "passive"))
      (node (ref "U1") (pin "J1") (pinfunction "IO_L22N_T3_35_J1") (pintype "bidirectional"))
      (node (ref "U1") (pin "K2") (pinfunction "IO_L24N_T3_35_K2") (pintype "bidirectional"))
    )
    (net (code "20") (name "/CAM_DOUT3_P") (class "Default")
      (node (ref "J2") (pin "11") (pintype "passive"))
      (node (ref "U1") (pin "K1") (pinfunction "IO_L22P_T3_35_K1") (pintype "bidirectional"))
      (node (ref "U1") (pin "K3") (pinfunction "IO_L24P_T3_35_K3") (pintype "bidirectional"))
    )
    (net (code "21") (name "/CAM_MON0") (class "Default")
      (node (ref "J2") (pin "4") (pintype "passive"))
      (node (ref "U1") (pin "P1") (pinfunction "IO_L4N_T0_34_P1") (pintype "bidirectional"))
    )
    (net (code "22") (name "/CAM_RESET") (class "Default")
      (node (ref "J2") (pin "3") (pintype "passive"))
      (node (ref "U1") (pin "R1") (pinfunction "IO_L7N_T1_34_R1") (pintype "bidirectional"))
    )
    (net (code "23") (name "/CAM_SPI_CLK") (class "Default")
      (node (ref "J2") (pin "43") (pintype "passive"))
      (node (ref "U1") (pin "C13") (pinfunction "IO_L12N_T1_MRCC_15_C13") (pintype "bidirectional"))
    )
    (net (code "24") (name "/CAM_SPI_CS") (class "Default")
      (node (ref "J2") (pin "44") (pintype "passive"))
      (node (ref "U1") (pin "B10") (pinfunction "IO_L4P_T0_15_B10") (pintype "bidirectional"))
    )
    (net (code "25") (name "/CAM_SPI_MISO") (class "Default")
      (node (ref "J2") (pin "45") (pintype "passive"))
      (node (ref "U1") (pin "B9") (pinfunction "IO_L3P_T0_DQS_AD1P_15_B9") (pintype "bidirectional"))
    )
    (net (code "26") (name "/CAM_SPI_MOSI") (class "Default")
      (node (ref "J2") (pin "47") (pintype "passive"))
      (node (ref "U1") (pin "C8") (pinfunction "IO_L1P_T0_AD0P_15_C8") (pintype "bidirectional"))
    )
    (net (code "27") (name "/CAM_SYNC_N") (class "Default")
      (node (ref "J2") (pin "9") (pintype "passive"))
      (node (ref "U1") (pin "L2") (pinfunction "IO_L23N_T3_35_L2") (pintype "bidirectional"))
    )
    (net (code "28") (name "/CAM_SYNC_P") (class "Default")
      (node (ref "J2") (pin "8") (pintype "passive"))
      (node (ref "U1") (pin "L3") (pinfunction "IO_L23P_T3_35_L3") (pintype "bidirectional"))
    )
    (net (code "29") (name "/CAM_TRIG0") (class "Default")
      (node (ref "J2") (pin "1") (pintype "passive"))
      (node (ref "U1") (pin "R2") (pinfunction "IO_L7P_T1_34_R2") (pintype "bidirectional"))
    )
    (net (code "30") (name "/CFGBVS") (class "Default")
      (node (ref "R2") (pin "1") (pinfunction "1_1") (pintype "passive"))
      (node (ref "U1") (pin "E7") (pinfunction "CFGBVS_0_E7") (pintype "input"))
    )
    (net (code "31") (name "/CONF_CLK") (class "Default")
      (node (ref "U1") (pin "P14") (pinfunction "IO_L12N_T1_MRCC_14_P14") (pintype "bidirectional"))
      (node (ref "U2") (pin "2") (pinfunction "SCLK_2") (pintype "output"))
    )
    (net (code "32") (name "/CONF_CS") (class "Default")
      (node (ref "R7") (pin "1") (pinfunction "1_1") (pintype "passive"))
      (node (ref "U1") (pin "N13") (pinfunction "IO_L11P_T1_SRCC_14_N13") (pintype "bidirectional"))
      (node (ref "U2") (pin "1") (pinfunction "~{CS}_1") (pintype "input"))
    )
    (net (code "33") (name "/CONF_MISO") (class "Default")
      (node (ref "R12") (pin "2") (pinfunction "2_2") (pintype "passive"))
      (node (ref "U1") (pin "P16") (pinfunction "IO_L8N_T1_D12_14_P16") (pintype "bidirectional"))
    )
    (net (code "34") (name "/CONF_MISO_NR") (class "Default")
      (node (ref "R12") (pin "1") (pinfunction "1_1") (pintype "passive"))
      (node (ref "U2") (pin "4") (pinfunction "MISO_4") (pintype "power_in"))
    )
    (net (code "35") (name "/CONF_MOSI") (class "Default")
      (node (ref "R9") (pin "2") (pinfunction "2_2") (pintype "passive"))
      (node (ref "U1") (pin "R16") (pinfunction "IO_L9N_T1_DQS_D13_14_R16") (pintype "bidirectional"))
    )
    (net (code "36") (name "/CONF_MOSI_NR") (class "Default")
      (node (ref "R9") (pin "1") (pinfunction "1_1") (pintype "passive"))
      (node (ref "U2") (pin "3") (pinfunction "MOSI_3") (pintype "input"))
    )
    (net (code "37") (name "/DONE") (class "Default")
      (node (ref "R5") (pin "1") (pinfunction "1_1") (pintype "passive"))
      (node (ref "R6") (pin "2") (pinfunction "2_2") (pintype "passive"))
      (node (ref "U1") (pin "H10") (pinfunction "DONE_0_H10") (pintype "bidirectional"))
    )
    (net (code "38") (name "/DONE_LED") (class "Default")
      (node (ref "D2") (pin "1") (pinfunction "1_1") (pintype "passive"))
      (node (ref "R6") (pin "1") (pinfunction "1_1") (pintype "passive"))
    )
    (net (code "39") (name "/FLASH_CLK") (class "Default")
      (node (ref "U1") (pin "E8") (pinfunction "CCLK_0_E8") (pintype "bidirectional"))
      (node (ref "U3") (pin "6") (pinfunction "CLK_6") (pintype "input"))
    )
    (net (code "40") (name "/FLASH_CS") (class "Default")
      (node (ref "R18") (pin "1") (pinfunction "1_1") (pintype "passive"))
      (node (ref "U1") (pin "L12") (pinfunction "IO_L6P_T0_FCS_B_14_L12") (pintype "bidirectional"))
      (node (ref "U3") (pin "1") (pinfunction "~{CS}_1") (pintype "input"))
    )
    (net (code "41") (name "/FLASH_D0") (class "Default")
      (node (ref "R20") (pin "2") (pinfunction "2_2") (pintype "passive"))
      (node (ref "U1") (pin "J13") (pinfunction "IO_L1P_T0_D00_MOSI_14_J13") (pintype "bidirectional"))
    )
    (net (code "42") (name "/FLASH_D0_NR") (class "Default")
      (node (ref "R20") (pin "1") (pinfunction "1_1") (pintype "passive"))
      (node (ref "U3") (pin "5") (pinfunction "DI(IO0)_5") (pintype "bidirectional"))
    )
    (net (code "43") (name "/FLASH_D1") (class "Default")
      (node (ref "R21") (pin "1") (pinfunction "1_1") (pintype "passive"))
      (node (ref "U1") (pin "J14") (pinfunction "IO_L1N_T0_D01_DIN_14_J14") (pintype "bidirectional"))
    )
    (net (code "44") (name "/FLASH_D1_NR") (class "Default")
      (node (ref "R21") (pin "2") (pinfunction "2_2") (pintype "passive"))
      (node (ref "U3") (pin "2") (pinfunction "DO(IO1)_2") (pintype "bidirectional"))
    )
    (net (code "45") (name "/FLASH_D2") (class "Default")
      (node (ref "R22") (pin "2") (pinfunction "2_2") (pintype "passive"))
      (node (ref "U1") (pin "K15") (pinfunction "IO_L2P_T0_D02_14_K15") (pintype "bidirectional"))
    )
    (net (code "46") (name "/FLASH_D2_NR") (class "Default")
      (node (ref "R16") (pin "1") (pinfunction "1_1") (pintype "passive"))
      (node (ref "R22") (pin "1") (pinfunction "1_1") (pintype "passive"))
      (node (ref "U3") (pin "3") (pinfunction "~{WP}(IO2)_3") (pintype "bidirectional"))
    )
    (net (code "47") (name "/FLASH_D3") (class "Default")
      (node (ref "R23") (pin "2") (pinfunction "2_2") (pintype "passive"))
      (node (ref "U1") (pin "K16") (pinfunction "IO_L2N_T0_D03_14_K16") (pintype "bidirectional"))
    )
    (net (code "48") (name "/FLASH_D3_NR") (class "Default")
      (node (ref "R17") (pin "1") (pinfunction "1_1") (pintype "passive"))
      (node (ref "R23") (pin "1") (pinfunction "1_1") (pintype "passive"))
      (node (ref "U3") (pin "7") (pinfunction "~{HOLD}/RESET(IO3)_7") (pintype "bidirectional"))
    )
    (net (code "49") (name "/FPGA_CLK") (class "Default")
      (node (ref "U1") (pin "N14") (pinfunction "IO_L12P_T1_MRCC_14_N14") (pintype "bidirectional"))
      (node (ref "X1") (pin "3") (pinfunction "OUT_3") (pintype "output"))
    )
    (net (code "50") (name "/INIT_B") (class "Default")
      (node (ref "R4") (pin "1") (pinfunction "1_1") (pintype "passive"))
      (node (ref "U1") (pin "K10") (pinfunction "INIT_B_0_K10") (pintype "bidirectional"))
    )
    (net (code "51") (name "/IR_FAULT") (class "Default")
      (node (ref "J2") (pin "49") (pintype "passive"))
      (node (ref "U1") (pin "T3") (pinfunction "IO_L9N_T1_DQS_34_T3") (pintype "bidirectional"))
    )
    (net (code "52") (name "/IR_PWM") (class "Default")
      (node (ref "J2") (pin "48") (pintype "passive"))
      (node (ref "U1") (pin "T2") (pinfunction "IO_L8N_T1_34_T2") (pintype "bidirectional"))
    )
    (net (code "53") (name "/LED_B") (class "Default")
      (node (ref "R14") (pin "1") (pinfunction "1_1") (pintype "passive"))
      (node (ref "U1") (pin "R15") (pinfunction "IO_L9P_T1_DQS_14_R15") (pintype "bidirectional"))
      (node (ref "U1") (pin "T15") (pinfunction "IO_L10N_T1_D15_14_T15") (pintype "bidirectional"))
    )
    (net (code "54") (name "/LED_B_CA") (class "Default")
      (node (ref "D1") (pin "5") (pinfunction "B_K_5") (pintype "passive"))
      (node (ref "R14") (pin "2") (pinfunction "2_2") (pintype "passive"))
    )
    (net (code "55") (name "/LED_G") (class "Default")
      (node (ref "R8") (pin "1") (pinfunction "1_1") (pintype "passive"))
      (node (ref "U1") (pin "R13") (pinfunction "IO_L16P_T2_CSI_B_14_R13") (pintype "bidirectional"))
      (node (ref "U1") (pin "T13") (pinfunction "IO_L16N_T2_A15_D31_14_T13") (pintype "bidirectional"))
    )
    (net (code "56") (name "/LED_G_CA") (class "Default")
      (node (ref "D1") (pin "3") (pinfunction "G_K_3") (pintype "passive"))
      (node (ref "R8") (pin "2") (pinfunction "2_2") (pintype "passive"))
    )
    (net (code "57") (name "/LED_R") (class "Default")
      (node (ref "R11") (pin "1") (pinfunction "1_1") (pintype "passive"))
      (node (ref "U1") (pin "P13") (pinfunction "IO_L11N_T1_SRCC_14_P13") (pintype "bidirectional"))
      (node (ref "U1") (pin "T14") (pinfunction "IO_L10P_T1_D14_14_T14") (pintype "bidirectional"))
    )
    (net (code "58") (name "/LED_R_CA") (class "Default")
      (node (ref "D1") (pin "4") (pinfunction "R_K_4") (pintype "passive"))
      (node (ref "R11") (pin "2") (pinfunction "2_2") (pintype "passive"))
    )
    (net (code "59") (name "/LED_USER") (class "Default")
      (node (ref "D3") (pin "1") (pinfunction "1_1") (pintype "passive"))
    )
    (net (code "60") (name "/LED_USER_DRAIN") (class "Default")
      (node (ref "D3") (pin "2") (pinfunction "2_2") (pintype "passive"))
      (node (ref "R24") (pin "1") (pinfunction "1_1") (pintype "passive"))
    )
    (net (code "61") (name "/MODE_0") (class "Default")
      (node (ref "R10") (pin "1") (pinfunction "1_1") (pintype "passive"))
      (node (ref "U1") (pin "M9") (pinfunction "M0_0_M9") (pintype "input"))
    )
    (net (code "62") (name "/MODE_1") (class "Default")
      (node (ref "R13") (pin "1") (pinfunction "1_1") (pintype "passive"))
      (node (ref "U1") (pin "M10") (pinfunction "M1_0_M10") (pintype "input"))
    )
    (net (code "63") (name "/MODE_2") (class "Default")
      (node (ref "R15") (pin "1") (pinfunction "1_1") (pintype "passive"))
      (node (ref "U1") (pin "M11") (pinfunction "M2_0_M11") (pintype "input"))
    )
    (net (code "64") (name "/PROGRAM_B") (class "Default")
      (node (ref "R3") (pin "1") (pinfunction "1_1") (pintype "passive"))
      (node (ref "U1") (pin "L9") (pinfunction "PROGRAM_B_0_L9") (pintype "input"))
    )
    (net (code "65") (name "/PUDC_B") (class "Default")
      (node (ref "R1") (pin "2") (pinfunction "2_2") (pintype "passive"))
      (node (ref "U1") (pin "L15") (pinfunction "IO_L3P_T0_DQS_PUDC_B_14_L15") (pintype "bidirectional"))
    )
    (net (code "66") (name "/PWR_12V_OFF") (class "Default")
      (node (ref "J1") (pin "47") (pintype "passive"))
      (node (ref "U1") (pin "C9") (pinfunction "IO_L1N_T0_AD0N_15_C9") (pintype "bidirectional"))
    )
    (net (code "67") (name "/RIO_CS") (class "Default")
      (node (ref "J1") (pin "23") (pintype "passive"))
      (node (ref "U1") (pin "B12") (pinfunction "IO_L5P_T0_AD9P_15_B12") (pintype "bidirectional"))
    )
    (net (code "68") (name "/RIO_MISO") (class "Default")
      (node (ref "J1") (pin "22") (pintype "passive"))
      (node (ref "U1") (pin "C11") (pinfunction "IO_L11P_T1_SRCC_15_C11") (pintype "bidirectional"))
    )
    (net (code "69") (name "/RIO_MOSI") (class "Default")
      (node (ref "J1") (pin "21") (pintype "passive"))
      (node (ref "U1") (pin "B11") (pinfunction "IO_L4N_T0_15_B11") (pintype "bidirectional"))
    )
    (net (code "70") (name "/RIO_SCLK") (class "Default")
      (node (ref "J1") (pin "20") (pintype "passive"))
      (node (ref "U1") (pin "E12") (pinfunction "IO_L13P_T2_MRCC_15_E12") (pintype "bidirectional"))
    )
    (net (code "71") (name "/USB_CLKOUT") (class "Default")
      (node (ref "J1") (pin "14") (pintype "passive"))
      (node (ref "U1") (pin "N11") (pinfunction "IO_L13P_T2_MRCC_14_N11") (pintype "bidirectional"))
    )
    (net (code "72") (name "/USB_D0") (class "Default")
      (node (ref "J1") (pin "1") (pintype "passive"))
      (node (ref "U1") (pin "T12") (pinfunction "IO_L15N_T2_DQS_DOUT_CSO_B_14_T12") (pintype "bidirectional"))
    )
    (net (code "73") (name "/USB_D1") (class "Default")
      (node (ref "J1") (pin "2") (pintype "passive"))
      (node (ref "U1") (pin "R12") (pinfunction "IO_L15P_T2_DQS_RDWR_B_14_R12") (pintype "bidirectional"))
    )
    (net (code "74") (name "/USB_D2") (class "Default")
      (node (ref "J1") (pin "3") (pintype "passive"))
      (node (ref "U1") (pin "R11") (pinfunction "IO_L17N_T2_A13_D29_14_R11") (pintype "bidirectional"))
    )
    (net (code "75") (name "/USB_D3") (class "Default")
      (node (ref "J1") (pin "4") (pintype "passive"))
      (node (ref "U1") (pin "T10") (pinfunction "IO_L22N_T3_A04_D20_14_T10") (pintype "bidirectional"))
    )
    (net (code "76") (name "/USB_D4") (class "Default")
      (node (ref "J1") (pin "5") (pintype "passive"))
      (node (ref "U1") (pin "R10") (pinfunction "IO_L17P_T2_A14_D30_14_R10") (pintype "bidirectional"))
    )
    (net (code "77") (name "/USB_D5") (class "Default")
      (node (ref "J1") (pin "6") (pintype "passive"))
      (node (ref "U1") (pin "T9") (pinfunction "IO_L22P_T3_A05_D21_14_T9") (pintype "bidirectional"))
    )
    (net (code "78") (name "/USB_D6") (class "Default")
      (node (ref "J1") (pin "7") (pintype "passive"))
      (node (ref "U1") (pin "P9") (pinfunction "IO_L18N_T2_A11_D27_14_P9") (pintype "bidirectional"))
    )
    (net (code "79") (name "/USB_D7") (class "Default")
      (node (ref "J1") (pin "8") (pintype "passive"))
      (node (ref "U1") (pin "T8") (pinfunction "IO_L21N_T3_DQS_A06_D22_14_T8") (pintype "bidirectional"))
    )
    (net (code "80") (name "/USB_OE") (class "Default")
      (node (ref "J1") (pin "15") (pintype "passive"))
      (node (ref "U1") (pin "N6") (pinfunction "IO_L19N_T3_A09_D25_VREF_14_N6") (pintype "bidirectional"))
    )
    (net (code "81") (name "/USB_RD") (class "Default")
      (node (ref "J1") (pin "11") (pintype "passive"))
      (node (ref "U1") (pin "R7") (pinfunction "IO_L24N_T3_A00_D16_14_R7") (pintype "bidirectional"))
    )
    (net (code "82") (name "/USB_RXF") (class "Default")
      (node (ref "J1") (pin "9") (pintype "passive"))
      (node (ref "U1") (pin "R8") (pinfunction "IO_L20N_T3_A07_D23_14_R8") (pintype "bidirectional"))
    )
    (net (code "83") (name "/USB_SIWU") (class "Default")
      (node (ref "J1") (pin "13") (pintype "passive"))
      (node (ref "U1") (pin "R6") (pinfunction "IO_L24P_T3_A01_D17_14_R6") (pintype "bidirectional"))
    )
    (net (code "84") (name "/USB_TCK") (class "Default")
      (node (ref "J1") (pin "19") (pintype "passive"))
      (node (ref "U1") (pin "L7") (pinfunction "TCK_0_L7") (pintype "input"))
    )
    (net (code "85") (name "/USB_TDI") (class "Default")
      (node (ref "J1") (pin "17") (pintype "passive"))
      (node (ref "U1") (pin "N7") (pinfunction "TDI_0_N7") (pintype "input"))
    )
    (net (code "86") (name "/USB_TDO") (class "Default")
      (node (ref "J1") (pin "16") (pintype "passive"))
      (node (ref "U1") (pin "N8") (pinfunction "TDO_0_N8") (pintype "output"))
    )
    (net (code "87") (name "/USB_TMS") (class "Default")
      (node (ref "J1") (pin "18") (pintype "passive"))
      (node (ref "U1") (pin "M7") (pinfunction "TMS_0_M7") (pintype "input"))
    )
    (net (code "88") (name "/USB_TXE") (class "Default")
      (node (ref "J1") (pin "10") (pintype "passive"))
      (node (ref "U1") (pin "T7") (pinfunction "IO_L21P_T3_DQS_14_T7") (pintype "bidirectional"))
    )
    (net (code "89") (name "/USB_WR") (class "Default")
      (node (ref "J1") (pin "12") (pintype "passive"))
      (node (ref "U1") (pin "R5") (pinfunction "IO_L23P_T3_A03_D19_14_R5") (pintype "bidirectional"))
    )
    (net (code "90") (name "AGND") (class "Default")
      (node (ref "C1") (pin "1") (pinfunction "1_1") (pintype "passive"))
      (node (ref "FB2") (pin "2") (pinfunction "2_2") (pintype "passive"))
      (node (ref "U1") (pin "G7") (pinfunction "GNDADC_0_G7") (pintype "power_in"))
      (node (ref "U1") (pin "H7") (pinfunction "VREFN_0_H7") (pintype "input"))
      (node (ref "U1") (pin "H8") (pinfunction "VP_0_H8") (pintype "input"))
      (node (ref "U1") (pin "J7") (pinfunction "VN_0_J7") (pintype "input"))
      (node (ref "U1") (pin "J8") (pinfunction "VREFP_0_J8") (pintype "input"))
    )
    (net (code "91") (name "ENC") (class "Default")
      (node (ref "M1") (pin "1") (pintype "passive"))
      (node (ref "M2") (pin "1") (pintype "passive"))
    )
    (net (code "92") (name "GND") (class "Default")
      (node (ref "C10") (pin "1") (pinfunction "1_1") (pintype "passive"))
      (node (ref "C11") (pin "2") (pinfunction "2_2") (pintype "passive"))
      (node (ref "C12") (pin "2") (pinfunction "2_2") (pintype "passive"))
      (node (ref "C13") (pin "2") (pinfunction "2_2") (pintype "passive"))
      (node (ref "C14") (pin "2") (pinfunction "2_2") (pintype "passive"))
      (node (ref "C15") (pin "2") (pinfunction "2_2") (pintype "passive"))
      (node (ref "C16") (pin "1") (pinfunction "1_1") (pintype "passive"))
      (node (ref "C17") (pin "1") (pinfunction "1_1") (pintype "passive"))
      (node (ref "C18") (pin "1") (pinfunction "1_1") (pintype "passive"))
      (node (ref "C19") (pin "2") (pinfunction "2_2") (pintype "passive"))
      (node (ref "C2") (pin "1") (pinfunction "1_1") (pintype "passive"))
      (node (ref "C20") (pin "2") (pinfunction "2_2") (pintype "passive"))
      (node (ref "C21") (pin "2") (pinfunction "2_2") (pintype "passive"))
      (node (ref "C22") (pin "2") (pinfunction "2_2") (pintype "passive"))
      (node (ref "C23") (pin "2") (pinfunction "2_2") (pintype "passive"))
      (node (ref "C24") (pin "2") (pinfunction "2_2") (pintype "passive"))
      (node (ref "C25") (pin "1") (pinfunction "1_1") (pintype "passive"))
      (node (ref "C26") (pin "1") (pinfunction "1_1") (pintype "passive"))
      (node (ref "C27") (pin "1") (pinfunction "1_1") (pintype "passive"))
      (node (ref "C29") (pin "1") (pinfunction "1_1") (pintype "passive"))
      (node (ref "C3") (pin "1") (pinfunction "1_1") (pintype "passive"))
      (node (ref "C30") (pin "1") (pinfunction "1_1") (pintype "passive"))
      (node (ref "C31") (pin "1") (pinfunction "1_1") (pintype "passive"))
      (node (ref "C32") (pin "1") (pinfunction "1_1") (pintype "passive"))
      (node (ref "C33") (pin "2") (pinfunction "2_2") (pintype "passive"))
      (node (ref "C34") (pin "2") (pinfunction "2_2") (pintype "passive"))
      (node (ref "C35") (pin "2") (pinfunction "2_2") (pintype "passive"))
      (node (ref "C36") (pin "2") (pinfunction "2_2") (pintype "passive"))
      (node (ref "C37") (pin "2") (pinfunction "2_2") (pintype "passive"))
      (node (ref "C38") (pin "2") (pinfunction "2_2") (pintype "passive"))
      (node (ref "C39") (pin "1") (pinfunction "1_1") (pintype "passive"))
      (node (ref "C4") (pin "1") (pinfunction "1_1") (pintype "passive"))
      (node (ref "C40") (pin "1") (pinfunction "1_1") (pintype "passive"))
      (node (ref "C41") (pin "1") (pinfunction "1_1") (pintype "passive"))
      (node (ref "C42") (pin "1") (pinfunction "1_1") (pintype "passive"))
      (node (ref "C43") (pin "1") (pinfunction "1_1") (pintype "passive"))
      (node (ref "C44") (pin "1") (pinfunction "1_1") (pintype "passive"))
      (node (ref "C45") (pin "1") (pinfunction "1_1") (pintype "passive"))
      (node (ref "C46") (pin "1") (pinfunction "1_1") (pintype "passive"))
      (node (ref "C47") (pin "1") (pinfunction "1_1") (pintype "passive"))
      (node (ref "C48") (pin "1") (pinfunction "1_1") (pintype "passive"))
      (node (ref "C5") (pin "1") (pinfunction "1_1") (pintype "passive"))
      (node (ref "C6") (pin "1") (pinfunction "1_1") (pintype "passive"))
      (node (ref "C7") (pin "1") (pinfunction "1_1") (pintype "passive"))
      (node (ref "C8") (pin "1") (pinfunction "1_1") (pintype "passive"))
      (node (ref "C9") (pin "1") (pinfunction "1_1") (pintype "passive"))
      (node (ref "D2") (pin "2") (pinfunction "2_2") (pintype "passive"))
      (node (ref "FB2") (pin "1") (pinfunction "1_1") (pintype "passive"))
      (node (ref "J1") (pin "24") (pintype "passive"))
      (node (ref "J1") (pin "26") (pintype "passive"))
      (node (ref "J1") (pin "27") (pintype "passive"))
      (node (ref "J1") (pin "28") (pintype "passive"))
      (node (ref "J1") (pin "30") (pintype "passive"))
      (node (ref "J1") (pin "33") (pintype "passive"))
      (node (ref "J1") (pin "36") (pintype "passive"))
      (node (ref "J1") (pin "39") (pintype "passive"))
      (node (ref "J1") (pin "42") (pintype "passive"))
      (node (ref "J1") (pin "44") (pintype "passive"))
      (node (ref "J1") (pin "45") (pintype "passive"))
      (node (ref "J1") (pin "46") (pintype "passive"))
      (node (ref "J1") (pin "49") (pintype "passive"))
      (node (ref "J1") (pin "MNT") (pintype "passive"))
      (node (ref "J2") (pin "10") (pintype "passive"))
      (node (ref "J2") (pin "13") (pintype "passive"))
      (node (ref "J2") (pin "16") (pintype "passive"))
      (node (ref "J2") (pin "19") (pintype "passive"))
      (node (ref "J2") (pin "2") (pintype "passive"))
      (node (ref "J2") (pin "22") (pintype "passive"))
      (node (ref "J2") (pin "25") (pintype "passive"))
      (node (ref "J2") (pin "28") (pintype "passive"))
      (node (ref "J2") (pin "29") (pintype "passive"))
      (node (ref "J2") (pin "33") (pintype "passive"))
      (node (ref "J2") (pin "36") (pintype "passive"))
      (node (ref "J2") (pin "37") (pintype "passive"))
      (node (ref "J2") (pin "39") (pintype "passive"))
      (node (ref "J2") (pin "41") (pintype "passive"))
      (node (ref "J2") (pin "42") (pintype "passive"))
      (node (ref "J2") (pin "46") (pintype "passive"))
      (node (ref "J2") (pin "6") (pintype "passive"))
      (node (ref "J2") (pin "7") (pintype "passive"))
      (node (ref "J2") (pin "MNT") (pintype "passive"))
      (node (ref "R13") (pin "2") (pinfunction "2_2") (pintype "passive"))
      (node (ref "R15") (pin "2") (pinfunction "2_2") (pintype "passive"))
      (node (ref "R24") (pin "2") (pinfunction "2_2") (pintype "passive"))
      (node (ref "U1") (pin "A1") (pinfunction "GND_A1") (pintype "power_in"))
      (node (ref "U1") (pin "A11") (pinfunction "GND_A11") (pintype "power_in"))
      (node (ref "U1") (pin "B8") (pinfunction "GND_B8") (pintype "power_in"))
      (node (ref "U1") (pin "C15") (pinfunction "GND_C15") (pintype "power_in"))
      (node (ref "U1") (pin "C5") (pinfunction "GND_C5") (pintype "power_in"))
      (node (ref "U1") (pin "D1") (pinfunction "IO_L10N_T1_AD15N_35_D1") (pintype "bidirectional"))
      (node (ref "U1") (pin "D12") (pinfunction "GND_D12") (pintype "power_in"))
      (node (ref "U1") (pin "D2") (pinfunction "GND_D2") (pintype "power_in"))
      (node (ref "U1") (pin "E9") (pinfunction "GND_E9") (pintype "power_in"))
      (node (ref "U1") (pin "F10") (pinfunction "GND_F10") (pintype "power_in"))
      (node (ref "U1") (pin "F16") (pinfunction "GND_F16") (pintype "power_in"))
      (node (ref "U1") (pin "F6") (pinfunction "GND_F6") (pintype "power_in"))
      (node (ref "U1") (pin "F8") (pinfunction "VCCBATT_0_F8") (pintype "power_in"))
      (node (ref "U1") (pin "G13") (pinfunction "GND_G13") (pintype "power_in"))
      (node (ref "U1") (pin "G3") (pinfunction "GND_G3") (pintype "power_in"))
      (node (ref "U1") (pin "G9") (pinfunction "GND_G9") (pintype "power_in"))
      (node (ref "U1") (pin "H6") (pinfunction "GND_H6") (pintype "power_in"))
      (node (ref "U1") (pin "J11") (pinfunction "GND_J11") (pintype "power_in"))
      (node (ref "U1") (pin "J9") (pinfunction "GND_J9") (pintype "power_in"))
      (node (ref "U1") (pin "K14") (pinfunction "GND_K14") (pintype "power_in"))
      (node (ref "U1") (pin "K4") (pinfunction "GND_K4") (pintype "power_in"))
      (node (ref "U1") (pin "K6") (pinfunction "GND_K6") (pintype "power_in"))
      (node (ref "U1") (pin "K7") (pinfunction "DXN_0_K7") (pintype "input"))
      (node (ref "U1") (pin "K8") (pinfunction "DXP_0_K8") (pintype "input"))
      (node (ref "U1") (pin "L1") (pinfunction "GND_L1") (pintype "power_in"))
      (node (ref "U1") (pin "L11") (pinfunction "GND_L11") (pintype "power_in"))
      (node (ref "U1") (pin "M8") (pinfunction "GND_M8") (pintype "power_in"))
      (node (ref "U1") (pin "N15") (pinfunction "GND_N15") (pintype "power_in"))
      (node (ref "U1") (pin "N5") (pinfunction "GND_N5") (pintype "power_in"))
      (node (ref "U1") (pin "P12") (pinfunction "GND_P12") (pintype "power_in"))
      (node (ref "U1") (pin "P2") (pinfunction "GND_P2") (pintype "power_in"))
      (node (ref "U1") (pin "R9") (pinfunction "GND_R9") (pintype "power_in"))
      (node (ref "U1") (pin "T16") (pinfunction "GND_T16") (pintype "power_in"))
      (node (ref "U1") (pin "T6") (pinfunction "GND_T6") (pintype "power_in"))
      (node (ref "U2") (pin "5") (pinfunction "GND_5") (pintype "input"))
      (node (ref "U2") (pin "9") (pinfunction "EPAD_9") (pintype "power_in"))
      (node (ref "U3") (pin "4") (pinfunction "GND_4") (pintype "power_in"))
      (node (ref "U3") (pin "9") (pinfunction "EP_9") (pintype "passive"))
      (node (ref "X1") (pin "2") (pinfunction "GND_2") (pintype "power_in"))
    )
    (net (code "93") (name "Net-(X1-OE)") (class "Default")
      (node (ref "R19") (pin "1") (pinfunction "1_1") (pintype "passive"))
      (node (ref "X1") (pin "1") (pinfunction "OE_1") (pintype "input"))
    )
    (net (code "94") (name "VCCADC") (class "Default")
      (node (ref "C1") (pin "2") (pinfunction "2_2") (pintype "passive"))
      (node (ref "C2") (pin "2") (pinfunction "2_2") (pintype "passive"))
      (node (ref "FB1") (pin "1") (pinfunction "1_1") (pintype "passive"))
      (node (ref "U1") (pin "G8") (pinfunction "VCCADC_0_G8") (pintype "power_in"))
    )
    (net (code "95") (name "unconnected-(U1A-IO_0_14-PadK12)") (class "Default")
      (node (ref "U1") (pin "K12") (pinfunction "IO_0_14_K12") (pintype "bidirectional"))
    )
    (net (code "96") (name "unconnected-(U1A-IO_25_14-PadP6)") (class "Default")
      (node (ref "U1") (pin "P6") (pinfunction "IO_25_14_P6") (pintype "bidirectional"))
    )
    (net (code "97") (name "unconnected-(U1A-IO_L3N_T0_DQS_EMCCLK_14-PadM15)") (class "Default")
      (node (ref "U1") (pin "M15") (pinfunction "IO_L3N_T0_DQS_EMCCLK_14_M15") (pintype "bidirectional+no_connect"))
    )
    (net (code "98") (name "unconnected-(U1A-IO_L4N_T0_D05_14-PadM14)") (class "Default")
      (node (ref "U1") (pin "M14") (pinfunction "IO_L4N_T0_D05_14_M14") (pintype "bidirectional"))
    )
    (net (code "99") (name "unconnected-(U1A-IO_L4P_T0_D04_14-PadL14)") (class "Default")
      (node (ref "U1") (pin "L14") (pinfunction "IO_L4P_T0_D04_14_L14") (pintype "bidirectional"))
    )
    (net (code "100") (name "unconnected-(U1A-IO_L5N_T0_D07_14-PadL13)") (class "Default")
      (node (ref "U1") (pin "L13") (pinfunction "IO_L5N_T0_D07_14_L13") (pintype "bidirectional"))
    )
    (net (code "101") (name "unconnected-(U1A-IO_L5P_T0_D06_14-PadK13)") (class "Default")
      (node (ref "U1") (pin "K13") (pinfunction "IO_L5P_T0_D06_14_K13") (pintype "bidirectional"))
    )
    (net (code "102") (name "unconnected-(U1A-IO_L6N_T0_D08_VREF_14-PadM12)") (class "Default")
      (node (ref "U1") (pin "M12") (pinfunction "IO_L6N_T0_D08_VREF_14_M12") (pintype "bidirectional"))
    )
    (net (code "103") (name "unconnected-(U1A-IO_L7N_T1_D10_14-PadN16)") (class "Default")
      (node (ref "U1") (pin "N16") (pinfunction "IO_L7N_T1_D10_14_N16") (pintype "bidirectional"))
    )
    (net (code "104") (name "unconnected-(U1A-IO_L7P_T1_D09_14-PadM16)") (class "Default")
      (node (ref "U1") (pin "M16") (pinfunction "IO_L7P_T1_D09_14_M16") (pintype "bidirectional"))
    )
    (net (code "105") (name "unconnected-(U1A-IO_L8P_T1_D11_14-PadP15)") (class "Default")
      (node (ref "U1") (pin "P15") (pinfunction "IO_L8P_T1_D11_14_P15") (pintype "bidirectional"))
    )
    (net (code "106") (name "unconnected-(U1A-IO_L13N_T2_MRCC_14-PadN12)") (class "Default")
      (node (ref "U1") (pin "N12") (pinfunction "IO_L13N_T2_MRCC_14_N12") (pintype "bidirectional"))
    )
    (net (code "107") (name "unconnected-(U1A-IO_L14N_T2_SRCC_14-PadP11)") (class "Default")
      (node (ref "U1") (pin "P11") (pinfunction "IO_L14N_T2_SRCC_14_P11") (pintype "bidirectional"))
    )
    (net (code "108") (name "unconnected-(U1A-IO_L14P_T2_SRCC_14-PadP10)") (class "Default")
      (node (ref "U1") (pin "P10") (pinfunction "IO_L14P_T2_SRCC_14_P10") (pintype "bidirectional"))
    )
    (net (code "109") (name "unconnected-(U1A-IO_L18P_T2_A12_D28_14-PadN9)") (class "Default")
      (node (ref "U1") (pin "N9") (pinfunction "IO_L18P_T2_A12_D28_14_N9") (pintype "bidirectional"))
    )
    (net (code "110") (name "unconnected-(U1A-IO_L19P_T3_A10_D26_14-PadM6)") (class "Default")
      (node (ref "U1") (pin "M6") (pinfunction "IO_L19P_T3_A10_D26_14_M6") (pintype "bidirectional"))
    )
    (net (code "111") (name "unconnected-(U1A-IO_L20P_T3_A08_D24_14-PadP8)") (class "Default")
      (node (ref "U1") (pin "P8") (pinfunction "IO_L20P_T3_A08_D24_14_P8") (pintype "bidirectional"))
    )
    (net (code "112") (name "unconnected-(U1A-IO_L23N_T3_A02_D18_14-PadT5)") (class "Default")
      (node (ref "U1") (pin "T5") (pinfunction "IO_L23N_T3_A02_D18_14_T5") (pintype "bidirectional"))
    )
    (net (code "113") (name "unconnected-(U1B-IO_0_15-PadD10)") (class "Default")
      (node (ref "U1") (pin "D10") (pinfunction "IO_0_15_D10") (pintype "bidirectional"))
    )
    (net (code "114") (name "unconnected-(U1B-IO_25_15-PadG11)") (class "Default")
      (node (ref "U1") (pin "G11") (pinfunction "IO_25_15_G11") (pintype "bidirectional"))
    )
    (net (code "115") (name "unconnected-(U1B-IO_L2N_T0_AD8N_15-PadA9)") (class "Default")
      (node (ref "U1") (pin "A9") (pinfunction "IO_L2N_T0_AD8N_15_A9") (pintype "bidirectional"))
    )
    (net (code "116") (name "unconnected-(U1B-IO_L2P_T0_AD8P_15-PadA8)") (class "Default")
      (node (ref "U1") (pin "A8") (pinfunction "IO_L2P_T0_AD8P_15_A8") (pintype "bidirectional"))
    )
    (net (code "117") (name "unconnected-(U1B-IO_L3N_T0_DQS_AD1N_15-PadA10)") (class "Default")
      (node (ref "U1") (pin "A10") (pinfunction "IO_L3N_T0_DQS_AD1N_15_A10") (pintype "bidirectional"))
    )
    (net (code "118") (name "unconnected-(U1B-IO_L5N_T0_AD9N_15-PadA12)") (class "Default")
      (node (ref "U1") (pin "A12") (pinfunction "IO_L5N_T0_AD9N_15_A12") (pintype "bidirectional"))
    )
    (net (code "119") (name "unconnected-(U1B-IO_L6N_T0_VREF_15-PadD9)") (class "Default")
      (node (ref "U1") (pin "D9") (pinfunction "IO_L6N_T0_VREF_15_D9") (pintype "bidirectional"))
    )
    (net (code "120") (name "unconnected-(U1B-IO_L6P_T0_15-PadD8)") (class "Default")
      (node (ref "U1") (pin "D8") (pinfunction "IO_L6P_T0_15_D8") (pintype "bidirectional"))
    )
    (net (code "121") (name "unconnected-(U1B-IO_L7N_T1_AD2N_15-PadA14)") (class "Default")
      (node (ref "U1") (pin "A14") (pinfunction "IO_L7N_T1_AD2N_15_A14") (pintype "bidirectional"))
    )
    (net (code "122") (name "unconnected-(U1B-IO_L7P_T1_AD2P_15-PadA13)") (class "Default")
      (node (ref "U1") (pin "A13") (pinfunction "IO_L7P_T1_AD2P_15_A13") (pintype "bidirectional"))
    )
    (net (code "123") (name "unconnected-(U1B-IO_L8N_T1_AD10N_15-PadB14)") (class "Default")
      (node (ref "U1") (pin "B14") (pinfunction "IO_L8N_T1_AD10N_15_B14") (pintype "bidirectional"))
    )
    (net (code "124") (name "unconnected-(U1B-IO_L8P_T1_AD10P_15-PadC14)") (class "Default")
      (node (ref "U1") (pin "C14") (pinfunction "IO_L8P_T1_AD10P_15_C14") (pintype "bidirectional"))
    )
    (net (code "125") (name "unconnected-(U1B-IO_L9N_T1_DQS_AD3N_15-PadA15)") (class "Default")
      (node (ref "U1") (pin "A15") (pinfunction "IO_L9N_T1_DQS_AD3N_15_A15") (pintype "bidirectional"))
    )
    (net (code "126") (name "unconnected-(U1B-IO_L9P_T1_DQS_AD3P_15-PadB15)") (class "Default")
      (node (ref "U1") (pin "B15") (pinfunction "IO_L9P_T1_DQS_AD3P_15_B15") (pintype "bidirectional"))
    )
    (net (code "127") (name "unconnected-(U1B-IO_L10N_T1_AD11N_15-PadB16)") (class "Default")
      (node (ref "U1") (pin "B16") (pinfunction "IO_L10N_T1_AD11N_15_B16") (pintype "bidirectional"))
    )
    (net (code "128") (name "unconnected-(U1B-IO_L10P_T1_AD11P_15-PadC16)") (class "Default")
      (node (ref "U1") (pin "C16") (pinfunction "IO_L10P_T1_AD11P_15_C16") (pintype "bidirectional"))
    )
    (net (code "129") (name "unconnected-(U1B-IO_L11N_T1_SRCC_15-PadC12)") (class "Default")
      (node (ref "U1") (pin "C12") (pinfunction "IO_L11N_T1_SRCC_15_C12") (pintype "bidirectional"))
    )
    (net (code "130") (name "unconnected-(U1B-IO_L12P_T1_MRCC_15-PadD13)") (class "Default")
      (node (ref "U1") (pin "D13") (pinfunction "IO_L12P_T1_MRCC_15_D13") (pintype "bidirectional"))
    )
    (net (code "131") (name "unconnected-(U1B-IO_L13N_T2_MRCC_15-PadE13)") (class "Default")
      (node (ref "U1") (pin "E13") (pinfunction "IO_L13N_T2_MRCC_15_E13") (pintype "bidirectional"))
    )
    (net (code "132") (name "unconnected-(U1B-IO_L14N_T2_SRCC_15-PadD11)") (class "Default")
      (node (ref "U1") (pin "D11") (pinfunction "IO_L14N_T2_SRCC_15_D11") (pintype "bidirectional"))
    )
    (net (code "133") (name "unconnected-(U1B-IO_L14P_T2_SRCC_15-PadE11)") (class "Default")
      (node (ref "U1") (pin "E11") (pinfunction "IO_L14P_T2_SRCC_15_E11") (pintype "bidirectional"))
    )
    (net (code "134") (name "unconnected-(U1B-IO_L15N_T2_DQS_ADV_B_15-PadD15)") (class "Default")
      (node (ref "U1") (pin "D15") (pinfunction "IO_L15N_T2_DQS_ADV_B_15_D15") (pintype "bidirectional"))
    )
    (net (code "135") (name "unconnected-(U1B-IO_L15P_T2_DQS_15-PadD14)") (class "Default")
      (node (ref "U1") (pin "D14") (pinfunction "IO_L15P_T2_DQS_15_D14") (pintype "bidirectional"))
    )
    (net (code "136") (name "unconnected-(U1B-IO_L16N_T2_A27_15-PadF13)") (class "Default")
      (node (ref "U1") (pin "F13") (pinfunction "IO_L16N_T2_A27_15_F13") (pintype "bidirectional"))
    )
    (net (code "137") (name "unconnected-(U1B-IO_L16P_T2_A28_15-PadF12)") (class "Default")
      (node (ref "U1") (pin "F12") (pinfunction "IO_L16P_T2_A28_15_F12") (pintype "bidirectional"))
    )
    (net (code "138") (name "unconnected-(U1B-IO_L17N_T2_A25_15-PadD16)") (class "Default")
      (node (ref "U1") (pin "D16") (pinfunction "IO_L17N_T2_A25_15_D16") (pintype "bidirectional"))
    )
    (net (code "139") (name "unconnected-(U1B-IO_L17P_T2_A26_15-PadE16)") (class "Default")
      (node (ref "U1") (pin "E16") (pinfunction "IO_L17P_T2_A26_15_E16") (pintype "bidirectional"))
    )
    (net (code "140") (name "unconnected-(U1B-IO_L18N_T2_A23_15-PadE15)") (class "Default")
      (node (ref "U1") (pin "E15") (pinfunction "IO_L18N_T2_A23_15_E15") (pintype "bidirectional"))
    )
    (net (code "141") (name "unconnected-(U1B-IO_L18P_T2_A24_15-PadF15)") (class "Default")
      (node (ref "U1") (pin "F15") (pinfunction "IO_L18P_T2_A24_15_F15") (pintype "bidirectional"))
    )
    (net (code "142") (name "unconnected-(U1B-IO_L19N_T3_A21_VREF_15-PadG12)") (class "Default")
      (node (ref "U1") (pin "G12") (pinfunction "IO_L19N_T3_A21_VREF_15_G12") (pintype "bidirectional"))
    )
    (net (code "143") (name "unconnected-(U1B-IO_L19P_T3_A22_15-PadH11)") (class "Default")
      (node (ref "U1") (pin "H11") (pinfunction "IO_L19P_T3_A22_15_H11") (pintype "bidirectional"))
    )
    (net (code "144") (name "unconnected-(U1B-IO_L20N_T3_A19_15-PadH13)") (class "Default")
      (node (ref "U1") (pin "H13") (pinfunction "IO_L20N_T3_A19_15_H13") (pintype "bidirectional"))
    )
    (net (code "145") (name "unconnected-(U1B-IO_L20P_T3_A20_15-PadH12)") (class "Default")
      (node (ref "U1") (pin "H12") (pinfunction "IO_L20P_T3_A20_15_H12") (pintype "bidirectional"))
    )
    (net (code "146") (name "unconnected-(U1B-IO_L21N_T3_DQS_A18_15-PadF14)") (class "Default")
      (node (ref "U1") (pin "F14") (pinfunction "IO_L21N_T3_DQS_A18_15_F14") (pintype "bidirectional"))
    )
    (net (code "147") (name "unconnected-(U1B-IO_L21P_T3_DQS_15-PadG14)") (class "Default")
      (node (ref "U1") (pin "G14") (pinfunction "IO_L21P_T3_DQS_15_G14") (pintype "bidirectional"))
    )
    (net (code "148") (name "unconnected-(U1B-IO_L22N_T3_A16_15-PadG16)") (class "Default")
      (node (ref "U1") (pin "G16") (pinfunction "IO_L22N_T3_A16_15_G16") (pintype "bidirectional"))
    )
    (net (code "149") (name "unconnected-(U1B-IO_L22P_T3_A17_15-PadH16)") (class "Default")
      (node (ref "U1") (pin "H16") (pinfunction "IO_L22P_T3_A17_15_H16") (pintype "bidirectional"))
    )
    (net (code "150") (name "unconnected-(U1B-IO_L23N_T3_FWE_B_15-PadJ16)") (class "Default")
      (node (ref "U1") (pin "J16") (pinfunction "IO_L23N_T3_FWE_B_15_J16") (pintype "bidirectional"))
    )
    (net (code "151") (name "unconnected-(U1B-IO_L23P_T3_FOE_B_15-PadJ15)") (class "Default")
      (node (ref "U1") (pin "J15") (pinfunction "IO_L23P_T3_FOE_B_15_J15") (pintype "bidirectional"))
    )
    (net (code "152") (name "unconnected-(U1B-IO_L24N_T3_RS0_15-PadG15)") (class "Default")
      (node (ref "U1") (pin "G15") (pinfunction "IO_L24N_T3_RS0_15_G15") (pintype "bidirectional"))
    )
    (net (code "153") (name "unconnected-(U1B-IO_L24P_T3_RS1_15-PadH14)") (class "Default")
      (node (ref "U1") (pin "H14") (pinfunction "IO_L24P_T3_RS1_15_H14") (pintype "bidirectional"))
    )
    (net (code "154") (name "unconnected-(U1C-IO_0_34-PadL5)") (class "Default")
      (node (ref "U1") (pin "L5") (pinfunction "IO_0_34_L5") (pintype "bidirectional"))
    )
    (net (code "155") (name "unconnected-(U1C-IO_L1N_T0_34-PadM4)") (class "Default")
      (node (ref "U1") (pin "M4") (pinfunction "IO_L1N_T0_34_M4") (pintype "bidirectional"))
    )
    (net (code "156") (name "unconnected-(U1C-IO_L1P_T0_34-PadL4)") (class "Default")
      (node (ref "U1") (pin "L4") (pinfunction "IO_L1P_T0_34_L4") (pintype "bidirectional"))
    )
    (net (code "157") (name "unconnected-(U1C-IO_L2N_T0_34-PadM1)") (class "Default")
      (node (ref "U1") (pin "M1") (pinfunction "IO_L2N_T0_34_M1") (pintype "bidirectional"))
    )
    (net (code "158") (name "unconnected-(U1C-IO_L2P_T0_34-PadM2)") (class "Default")
      (node (ref "U1") (pin "M2") (pinfunction "IO_L2P_T0_34_M2") (pintype "bidirectional"))
    )
    (net (code "159") (name "unconnected-(U1C-IO_L3N_T0_DQS_34-PadN2)") (class "Default")
      (node (ref "U1") (pin "N2") (pinfunction "IO_L3N_T0_DQS_34_N2") (pintype "bidirectional"))
    )
    (net (code "160") (name "unconnected-(U1C-IO_L3P_T0_DQS_34-PadN3)") (class "Default")
      (node (ref "U1") (pin "N3") (pinfunction "IO_L3P_T0_DQS_34_N3") (pintype "bidirectional"))
    )
    (net (code "161") (name "unconnected-(U1C-IO_L5N_T0_34-PadP3)") (class "Default")
      (node (ref "U1") (pin "P3") (pinfunction "IO_L5N_T0_34_P3") (pintype "bidirectional"))
    )
    (net (code "162") (name "unconnected-(U1C-IO_L5P_T0_34-PadP4)") (class "Default")
      (node (ref "U1") (pin "P4") (pinfunction "IO_L5P_T0_34_P4") (pintype "bidirectional"))
    )
    (net (code "163") (name "unconnected-(U1C-IO_L6N_T0_VREF_34-PadN4)") (class "Default")
      (node (ref "U1") (pin "N4") (pinfunction "IO_L6N_T0_VREF_34_N4") (pintype "bidirectional"))
    )
    (net (code "164") (name "unconnected-(U1C-IO_L6P_T0_34-PadM5)") (class "Default")
      (node (ref "U1") (pin "M5") (pinfunction "IO_L6P_T0_34_M5") (pintype "bidirectional"))
    )
    (net (code "165") (name "unconnected-(U1C-IO_L8P_T1_34-PadR3)") (class "Default")
      (node (ref "U1") (pin "R3") (pinfunction "IO_L8P_T1_34_R3") (pintype "bidirectional"))
    )
    (net (code "166") (name "unconnected-(U1C-IO_L9P_T1_DQS_34-PadT4)") (class "Default")
      (node (ref "U1") (pin "T4") (pinfunction "IO_L9P_T1_DQS_34_T4") (pintype "bidirectional"))
    )
    (net (code "167") (name "unconnected-(U1C-IO_L10P_T1_34-PadP5)") (class "Default")
      (node (ref "U1") (pin "P5") (pinfunction "IO_L10P_T1_34_P5") (pintype "bidirectional"))
    )
    (net (code "168") (name "unconnected-(U1D-IO_0_35-PadE6)") (class "Default")
      (node (ref "U1") (pin "E6") (pinfunction "IO_0_35_E6") (pintype "bidirectional"))
    )
    (net (code "169") (name "unconnected-(U1D-IO_25_35-PadK5)") (class "Default")
      (node (ref "U1") (pin "K5") (pinfunction "IO_25_35_K5") (pintype "bidirectional"))
    )
    (net (code "170") (name "unconnected-(U1D-IO_L1N_T0_AD4N_35-PadA7)") (class "Default")
      (node (ref "U1") (pin "A7") (pinfunction "IO_L1N_T0_AD4N_35_A7") (pintype "bidirectional"))
    )
    (net (code "171") (name "unconnected-(U1D-IO_L1P_T0_AD4P_35-PadB7)") (class "Default")
      (node (ref "U1") (pin "B7") (pinfunction "IO_L1P_T0_AD4P_35_B7") (pintype "bidirectional"))
    )
    (net (code "172") (name "unconnected-(U1D-IO_L2N_T0_AD12N_35-PadB5)") (class "Default")
      (node (ref "U1") (pin "B5") (pinfunction "IO_L2N_T0_AD12N_35_B5") (pintype "bidirectional"))
    )
    (net (code "173") (name "unconnected-(U1D-IO_L2P_T0_AD12P_35-PadB6)") (class "Default")
      (node (ref "U1") (pin "B6") (pinfunction "IO_L2P_T0_AD12P_35_B6") (pintype "bidirectional"))
    )
    (net (code "174") (name "unconnected-(U1D-IO_L3N_T0_DQS_AD5N_35-PadA4)") (class "Default")
      (node (ref "U1") (pin "A4") (pinfunction "IO_L3N_T0_DQS_AD5N_35_A4") (pintype "bidirectional"))
    )
    (net (code "175") (name "unconnected-(U1D-IO_L3P_T0_DQS_AD5P_35-PadA5)") (class "Default")
      (node (ref "U1") (pin "A5") (pinfunction "IO_L3P_T0_DQS_AD5P_35_A5") (pintype "bidirectional"))
    )
    (net (code "176") (name "unconnected-(U1D-IO_L4N_T0_35-PadA3)") (class "Default")
      (node (ref "U1") (pin "A3") (pinfunction "IO_L4N_T0_35_A3") (pintype "bidirectional"))
    )
    (net (code "177") (name "unconnected-(U1D-IO_L4P_T0_35-PadB4)") (class "Default")
      (node (ref "U1") (pin "B4") (pinfunction "IO_L4P_T0_35_B4") (pintype "bidirectional"))
    )
    (net (code "178") (name "unconnected-(U1D-IO_L5N_T0_AD13N_35-PadC6)") (class "Default")
      (node (ref "U1") (pin "C6") (pinfunction "IO_L5N_T0_AD13N_35_C6") (pintype "bidirectional"))
    )
    (net (code "179") (name "unconnected-(U1D-IO_L5P_T0_AD13P_35-PadC7)") (class "Default")
      (node (ref "U1") (pin "C7") (pinfunction "IO_L5P_T0_AD13P_35_C7") (pintype "bidirectional"))
    )
    (net (code "180") (name "unconnected-(U1D-IO_L6N_T0_VREF_35-PadD5)") (class "Default")
      (node (ref "U1") (pin "D5") (pinfunction "IO_L6N_T0_VREF_35_D5") (pintype "bidirectional"))
    )
    (net (code "181") (name "unconnected-(U1D-IO_L6P_T0_35-PadD6)") (class "Default")
      (node (ref "U1") (pin "D6") (pinfunction "IO_L6P_T0_35_D6") (pintype "bidirectional"))
    )
    (net (code "182") (name "unconnected-(U1D-IO_L8N_T1_AD14N_35-PadA2)") (class "Default")
      (node (ref "U1") (pin "A2") (pinfunction "IO_L8N_T1_AD14N_35_A2") (pintype "bidirectional"))
    )
    (net (code "183") (name "unconnected-(U1D-IO_L8P_T1_AD14P_35-PadB2)") (class "Default")
      (node (ref "U1") (pin "B2") (pinfunction "IO_L8P_T1_AD14P_35_B2") (pintype "bidirectional"))
    )
    (net (code "184") (name "unconnected-(U1D-IO_L9N_T1_DQS_AD7N_35-PadB1)") (class "Default")
      (node (ref "U1") (pin "B1") (pinfunction "IO_L9N_T1_DQS_AD7N_35_B1") (pintype "bidirectional"))
    )
    (net (code "185") (name "unconnected-(U1D-IO_L15P_T2_DQS_35-PadF2)") (class "Default")
      (node (ref "U1") (pin "F2") (pinfunction "IO_L15P_T2_DQS_35_F2") (pintype "bidirectional"))
    )
    (net (code "186") (name "unconnected-(U1D-IO_L16N_T2_35-PadG4)") (class "Default")
      (node (ref "U1") (pin "G4") (pinfunction "IO_L16N_T2_35_G4") (pintype "bidirectional"))
    )
    (net (code "187") (name "unconnected-(U1D-IO_L16P_T2_35-PadG5)") (class "Default")
      (node (ref "U1") (pin "G5") (pinfunction "IO_L16P_T2_35_G5") (pintype "bidirectional"))
    )
    (net (code "188") (name "unconnected-(U1D-IO_L18N_T2_35-PadH4)") (class "Default")
      (node (ref "U1") (pin "H4") (pinfunction "IO_L18N_T2_35_H4") (pintype "bidirectional"))
    )
    (net (code "189") (name "unconnected-(U1D-IO_L18P_T2_35-PadH5)") (class "Default")
      (node (ref "U1") (pin "H5") (pinfunction "IO_L18P_T2_35_H5") (pintype "bidirectional"))
    )
    (net (code "190") (name "unconnected-(U1D-IO_L19N_T3_VREF_35-PadJ4)") (class "Default")
      (node (ref "U1") (pin "J4") (pinfunction "IO_L19N_T3_VREF_35_J4") (pintype "bidirectional"))
    )
    (net (code "191") (name "unconnected-(U1D-IO_L19P_T3_35-PadJ5)") (class "Default")
      (node (ref "U1") (pin "J5") (pinfunction "IO_L19P_T3_35_J5") (pintype "bidirectional"))
    )
    (net (code "192") (name "unconnected-(U2-NC-Pad7)") (class "Default")
      (node (ref "U2") (pin "7") (pinfunction "NC_7") (pintype "input+no_connect"))
    )
  )
)
